# mt7621_integrated_router_v2_6_2025-04-17.net
KiCad netlist of a schematic drawn in EasyEDA Pro
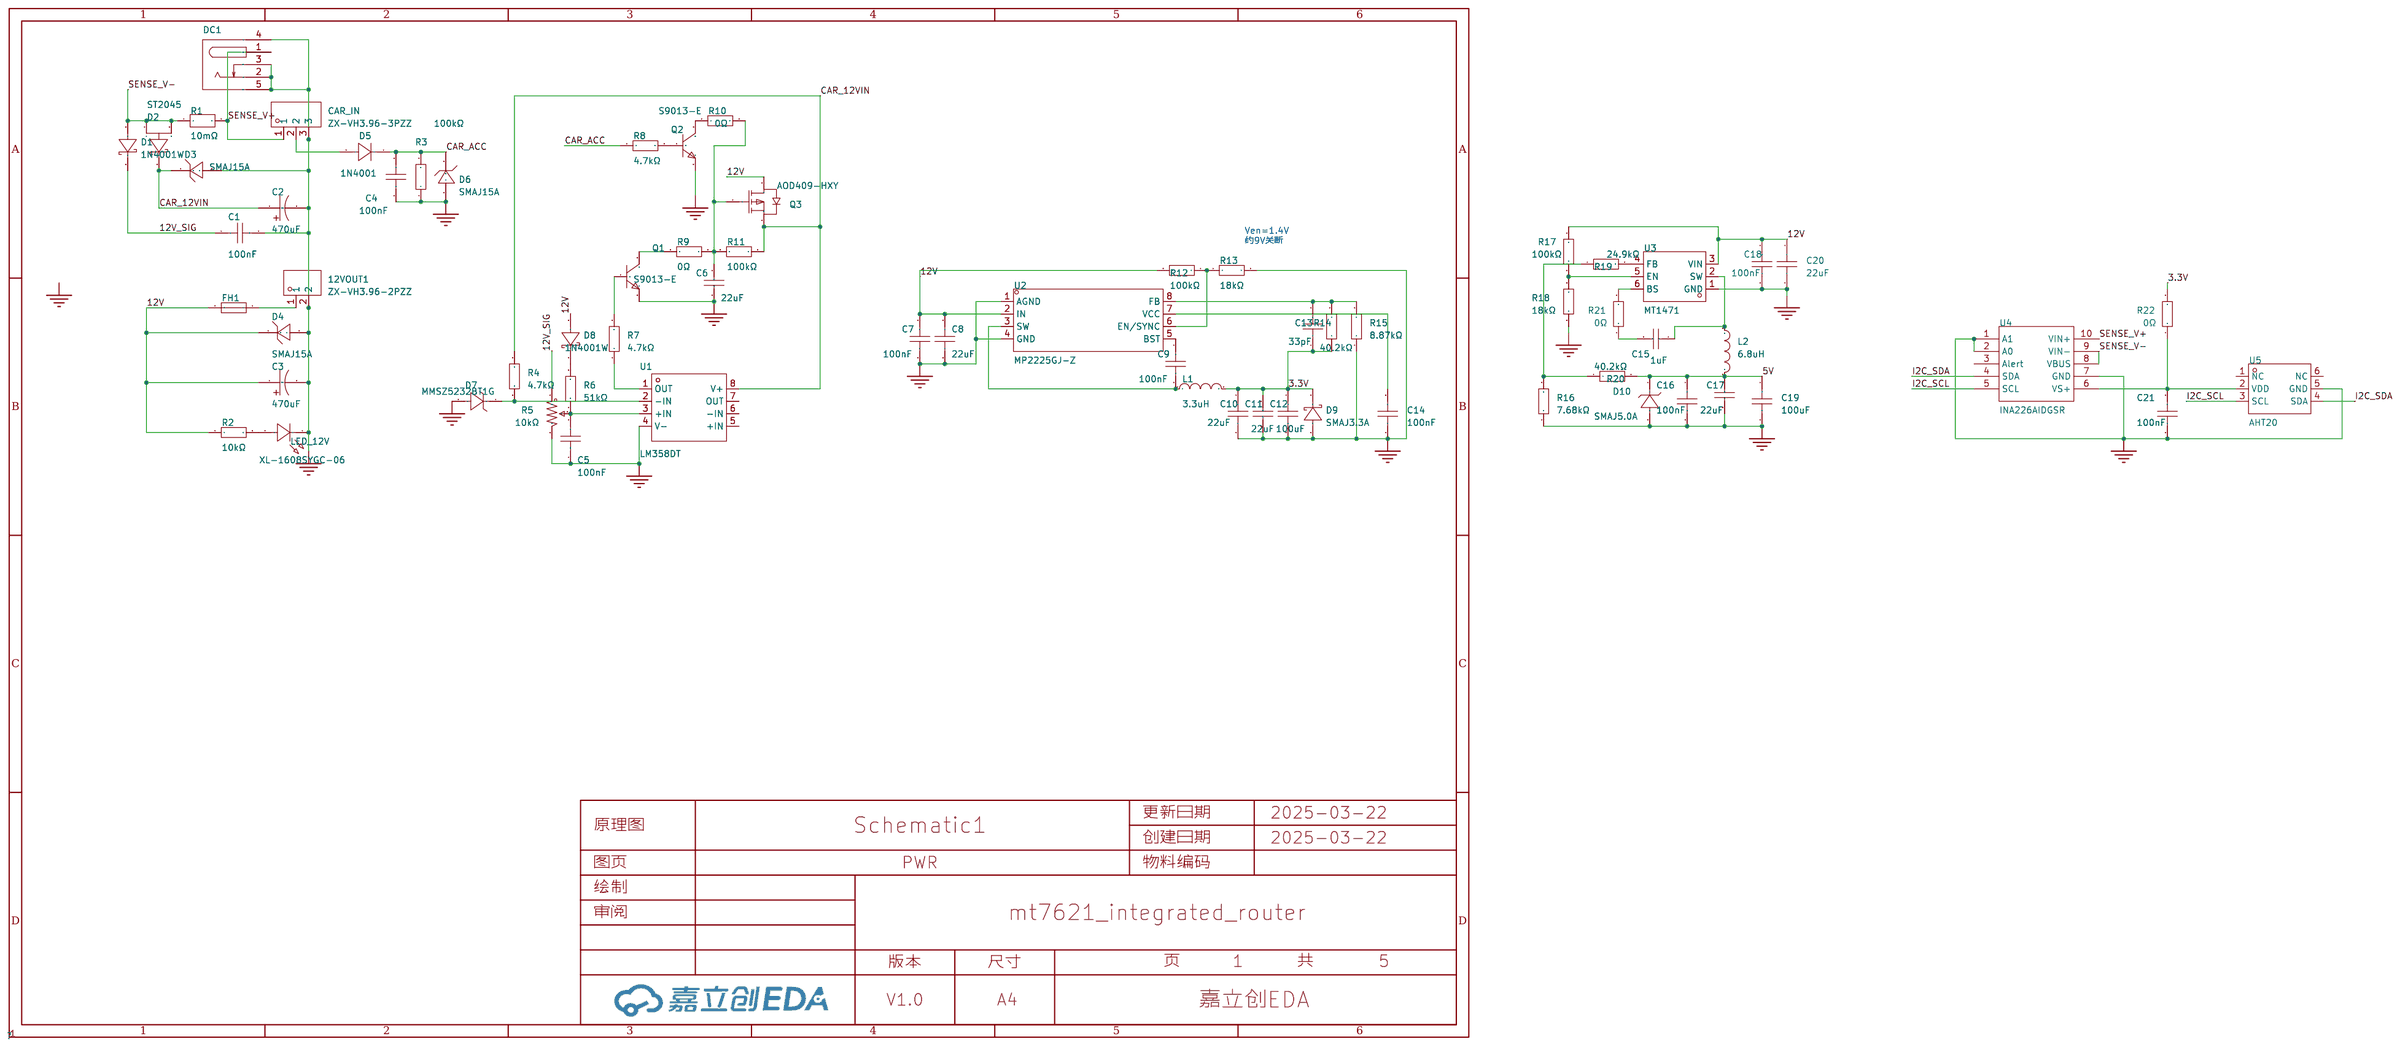
[diagram p0: PWR]
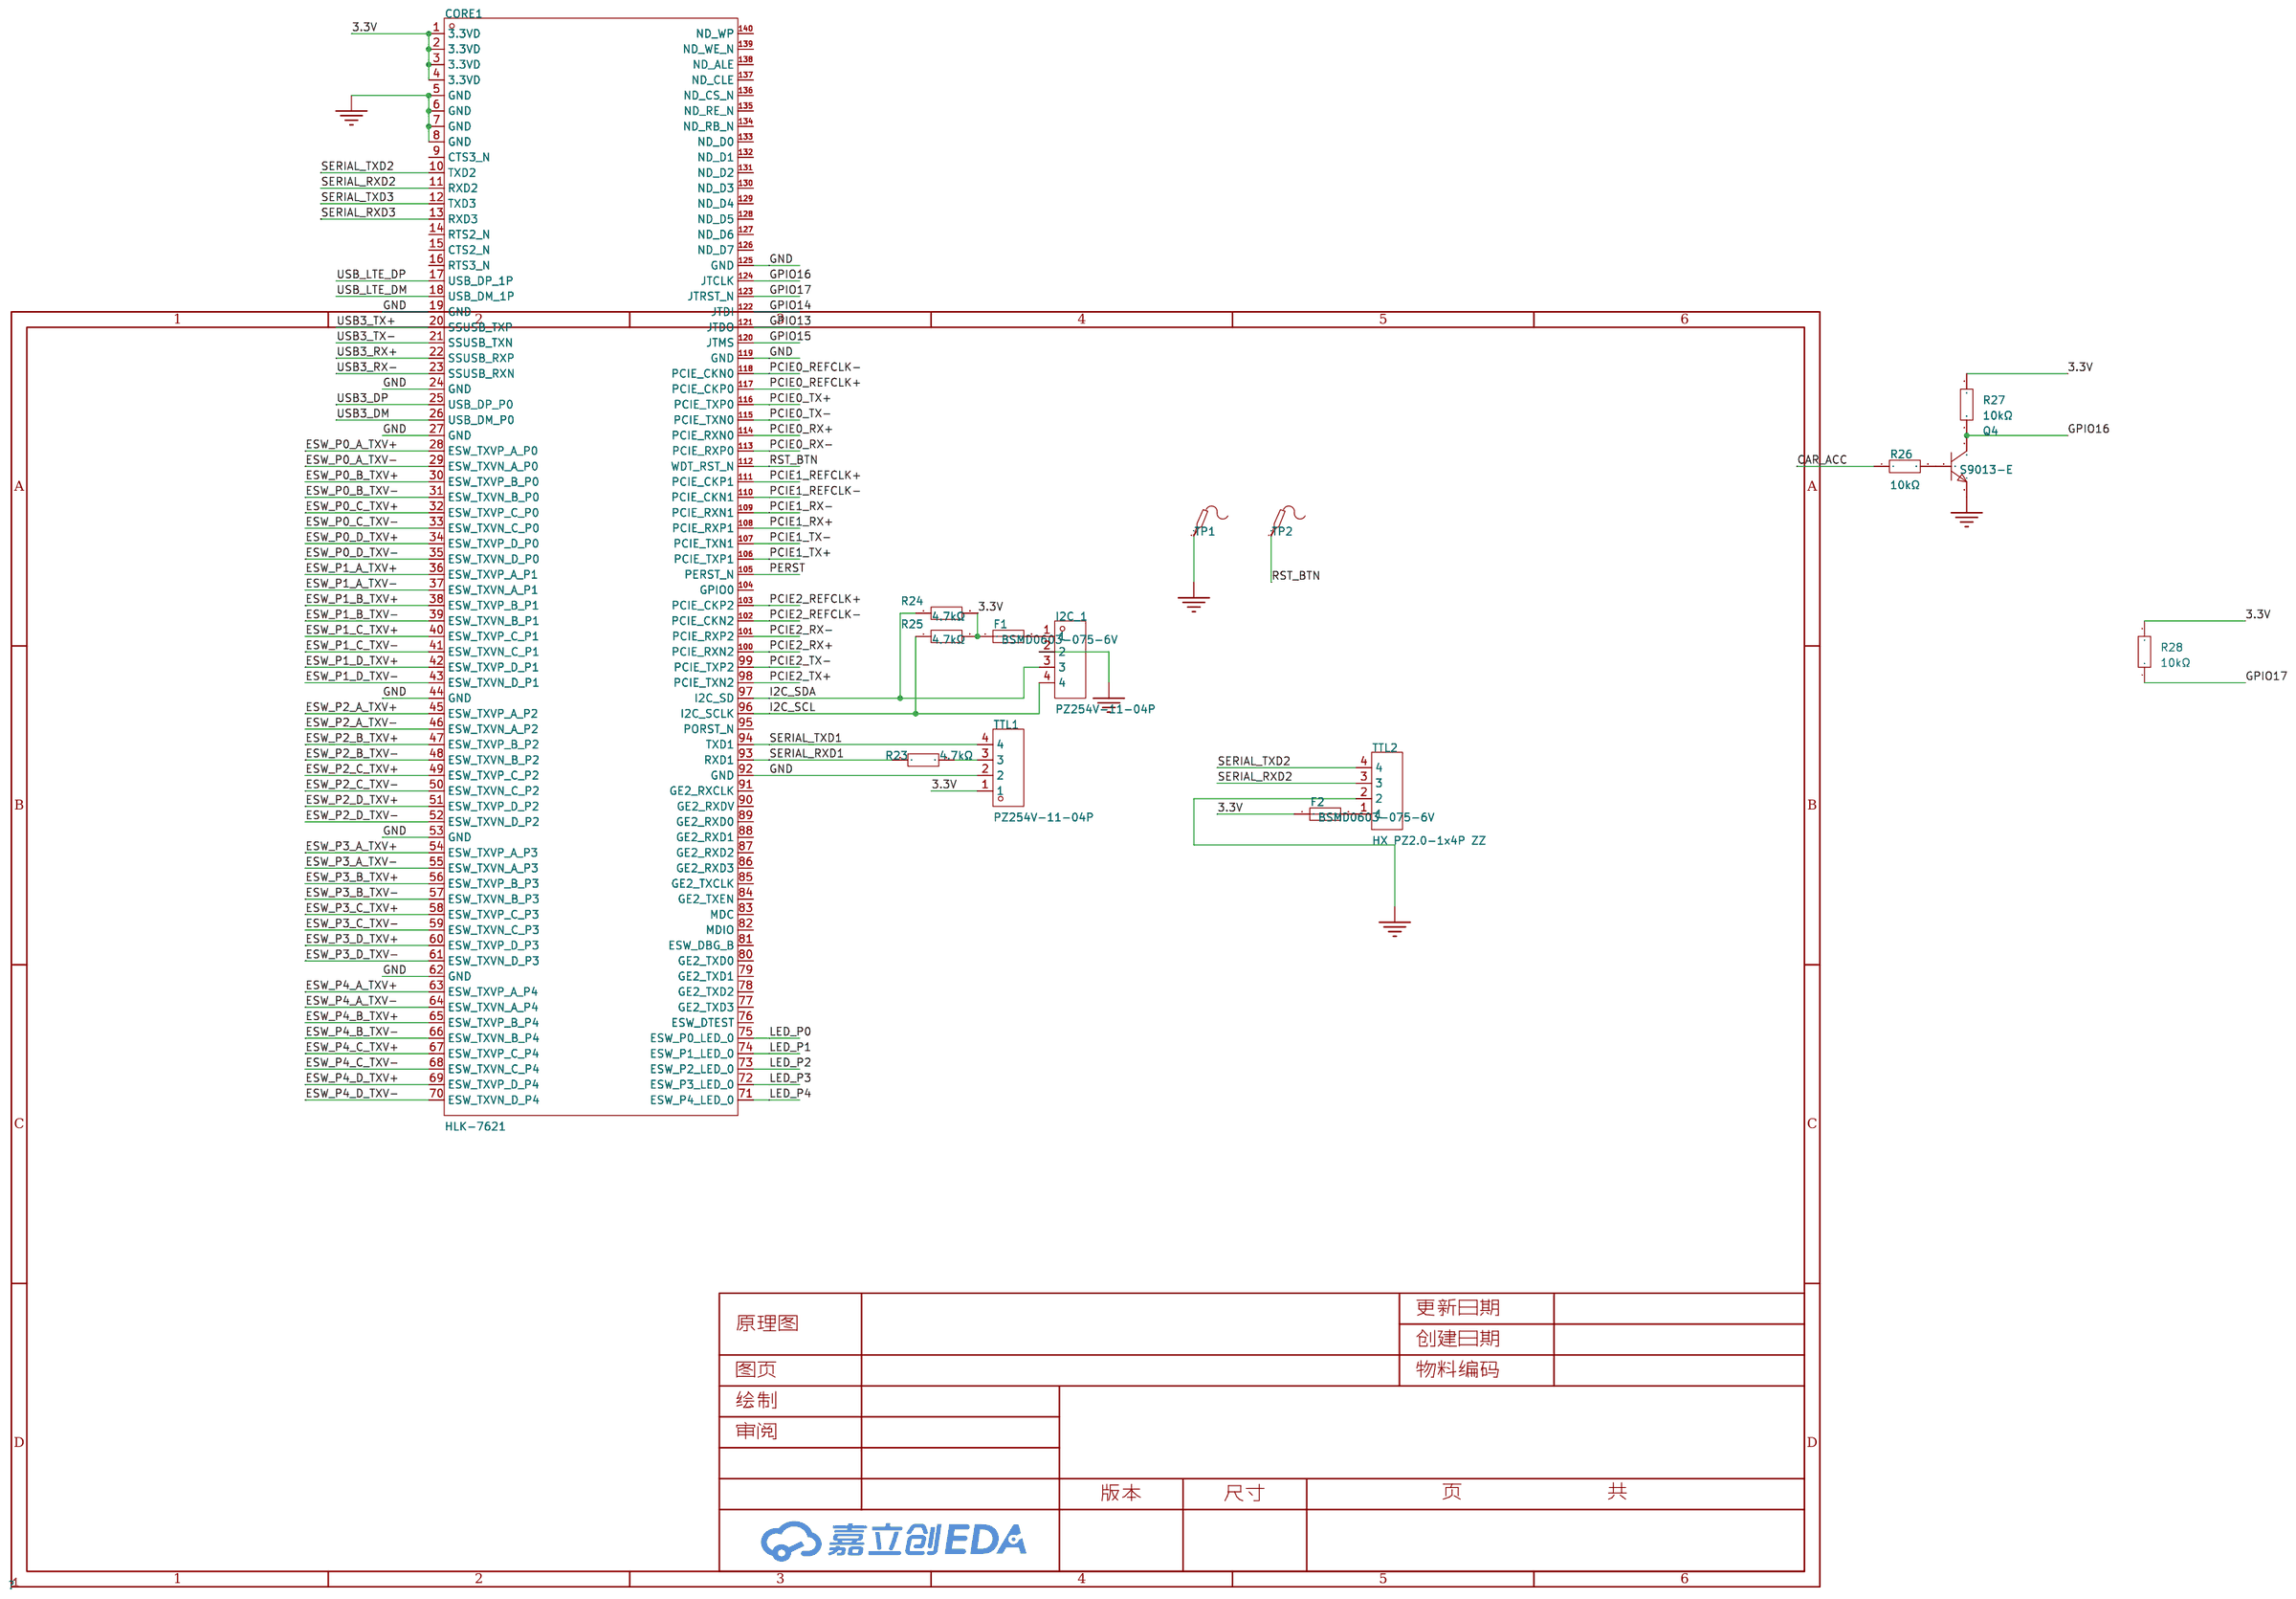
[diagram p1: Router]
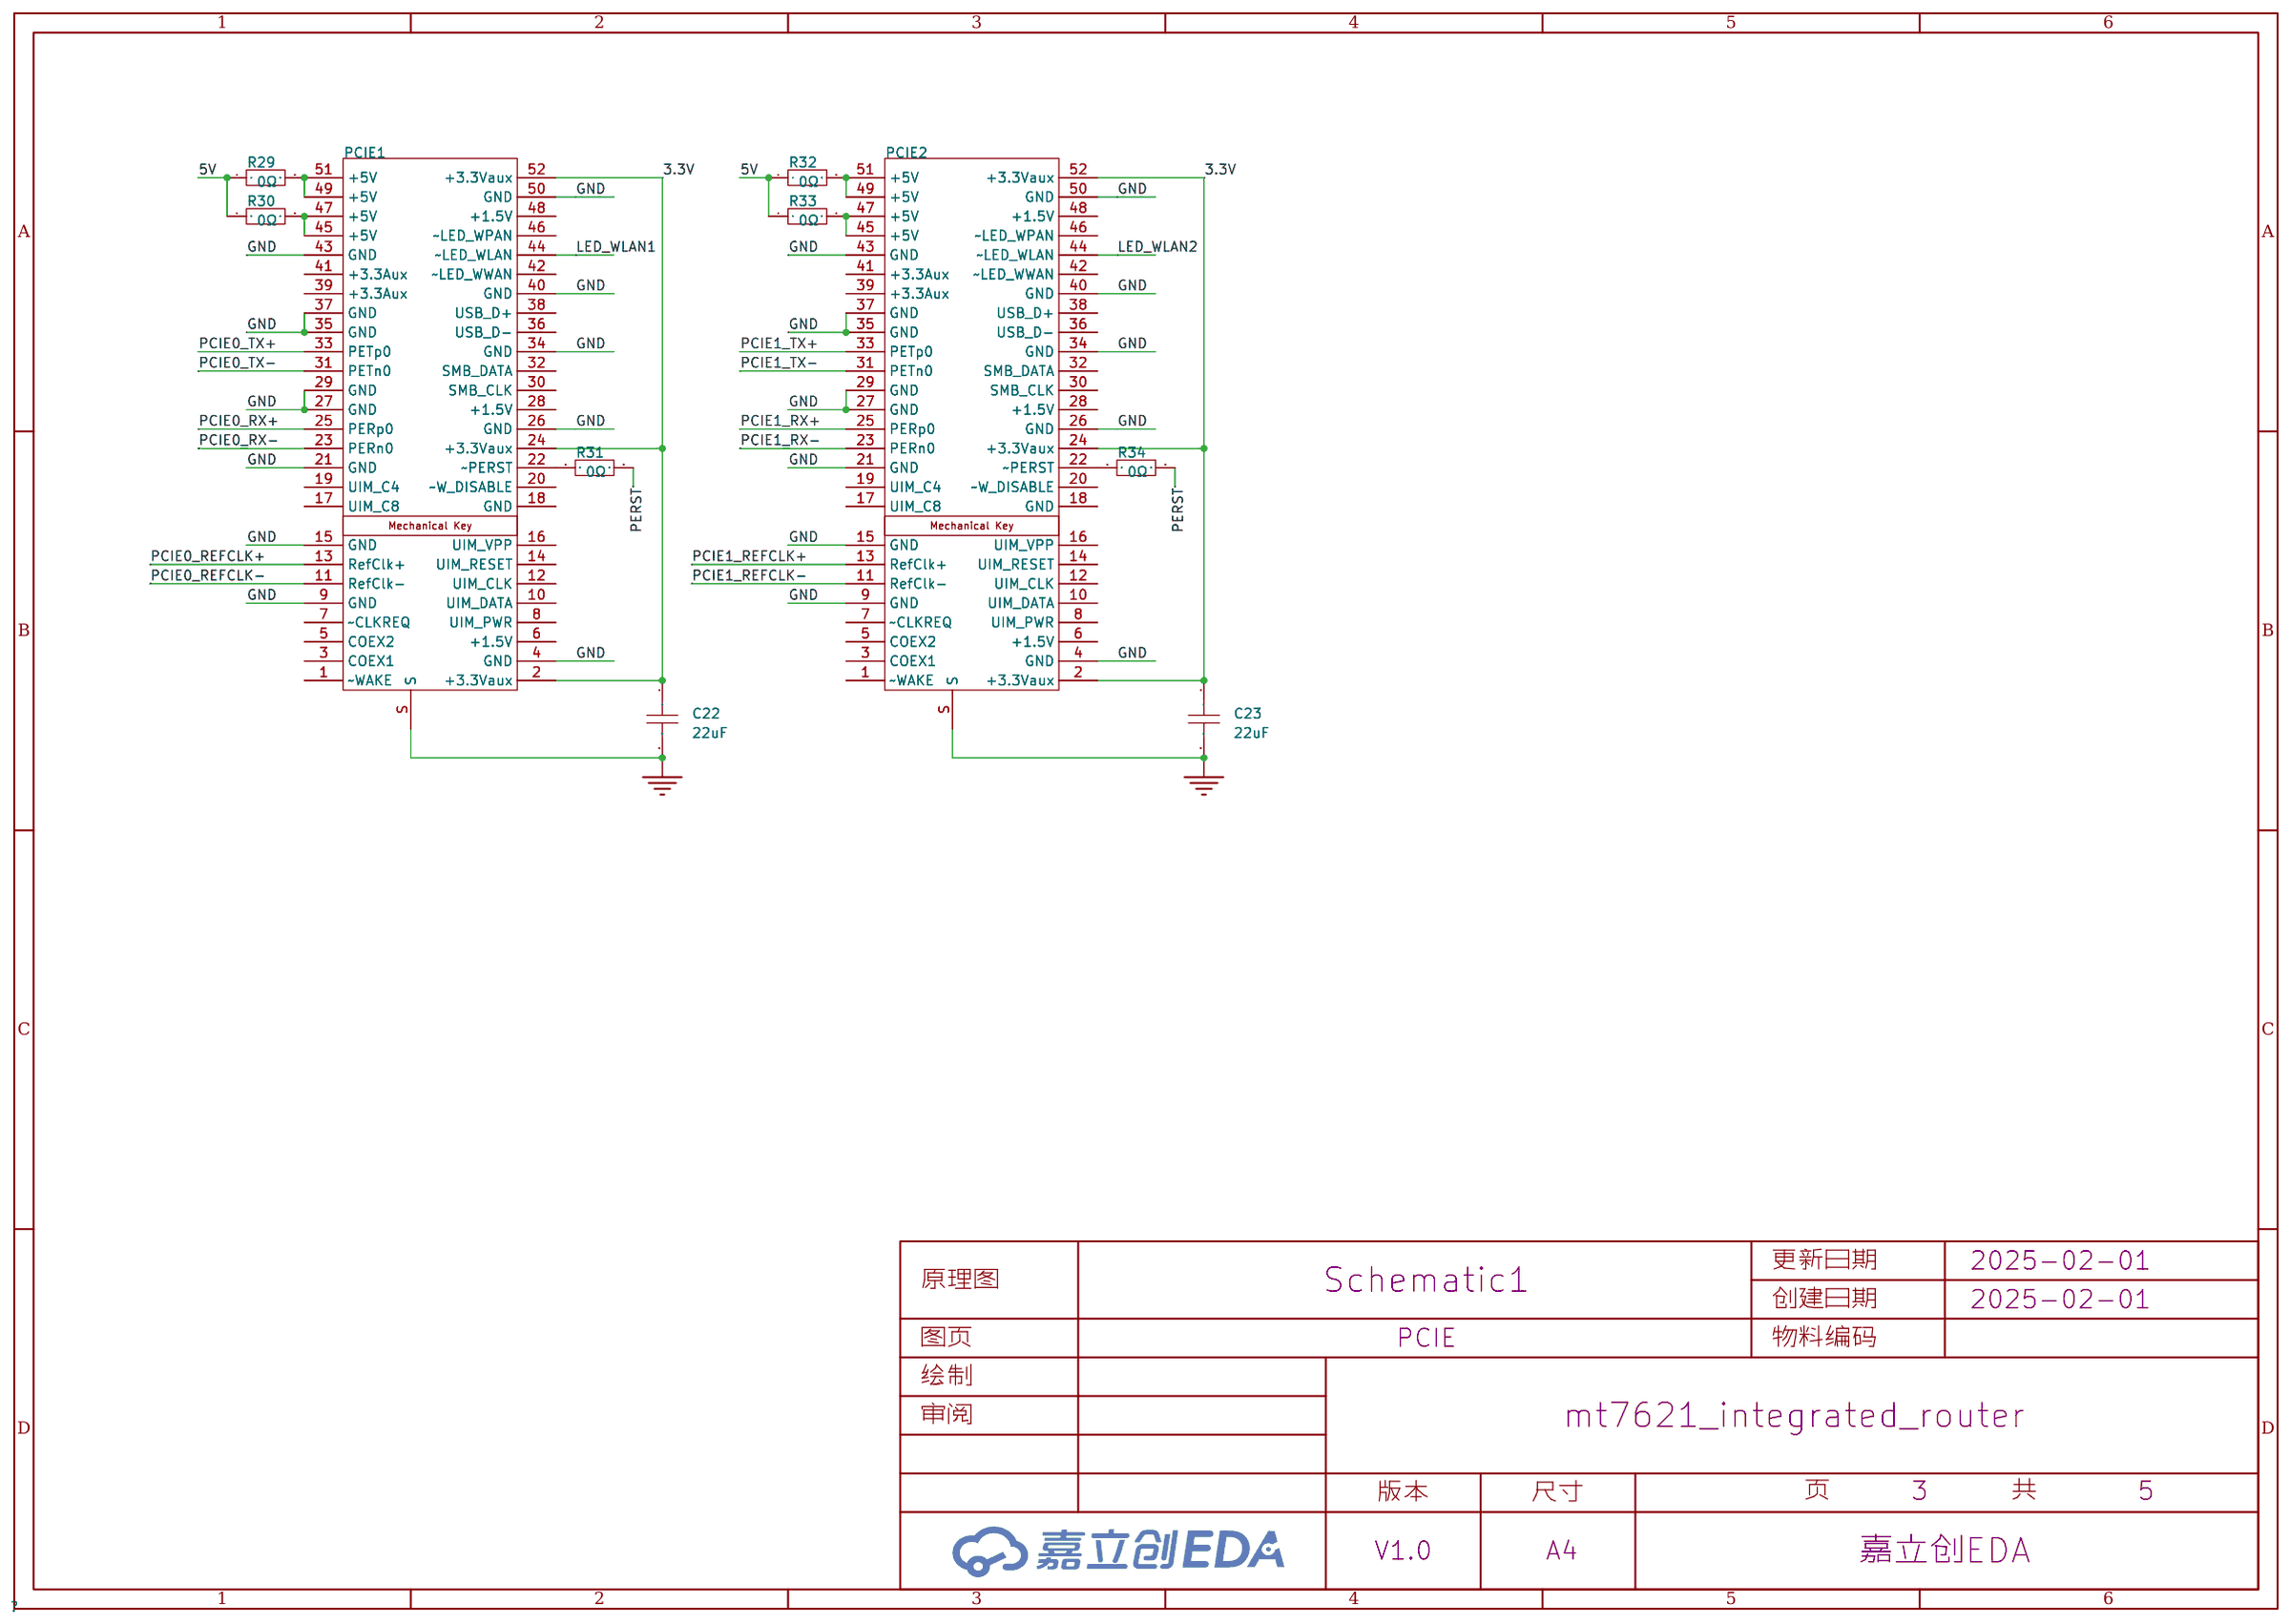
[diagram p2: PCIE]
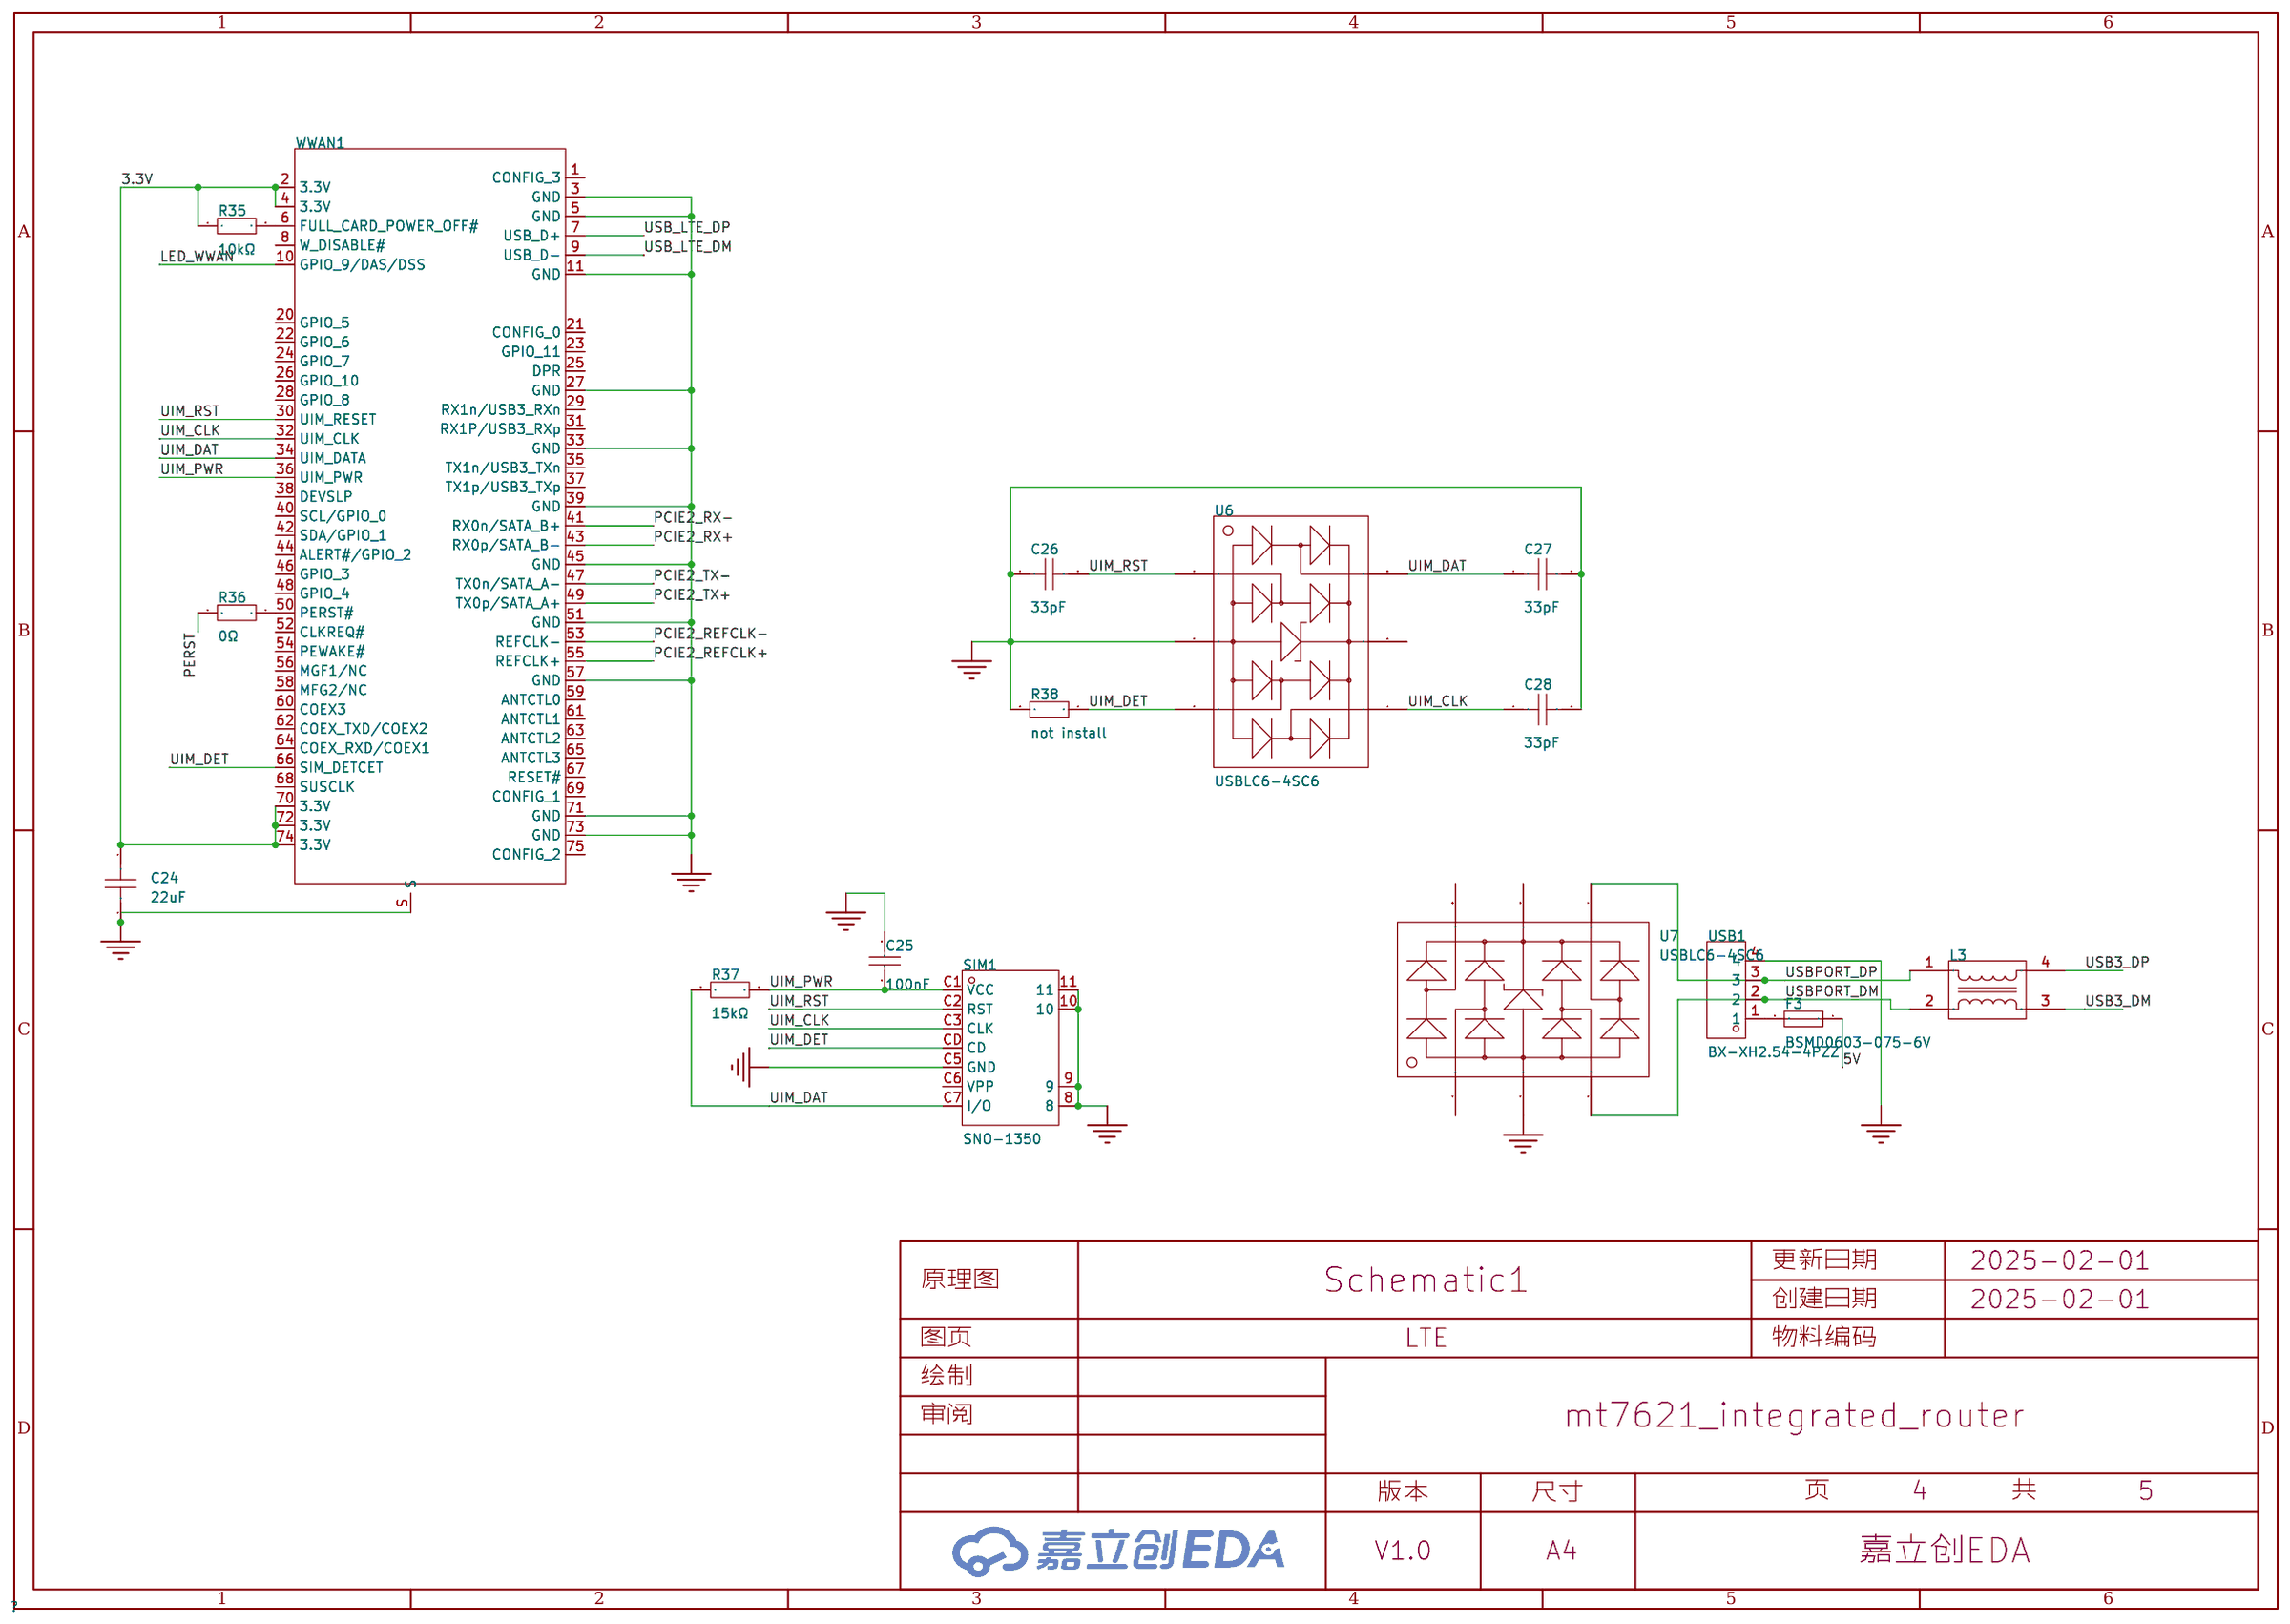
[diagram p3: LTE]
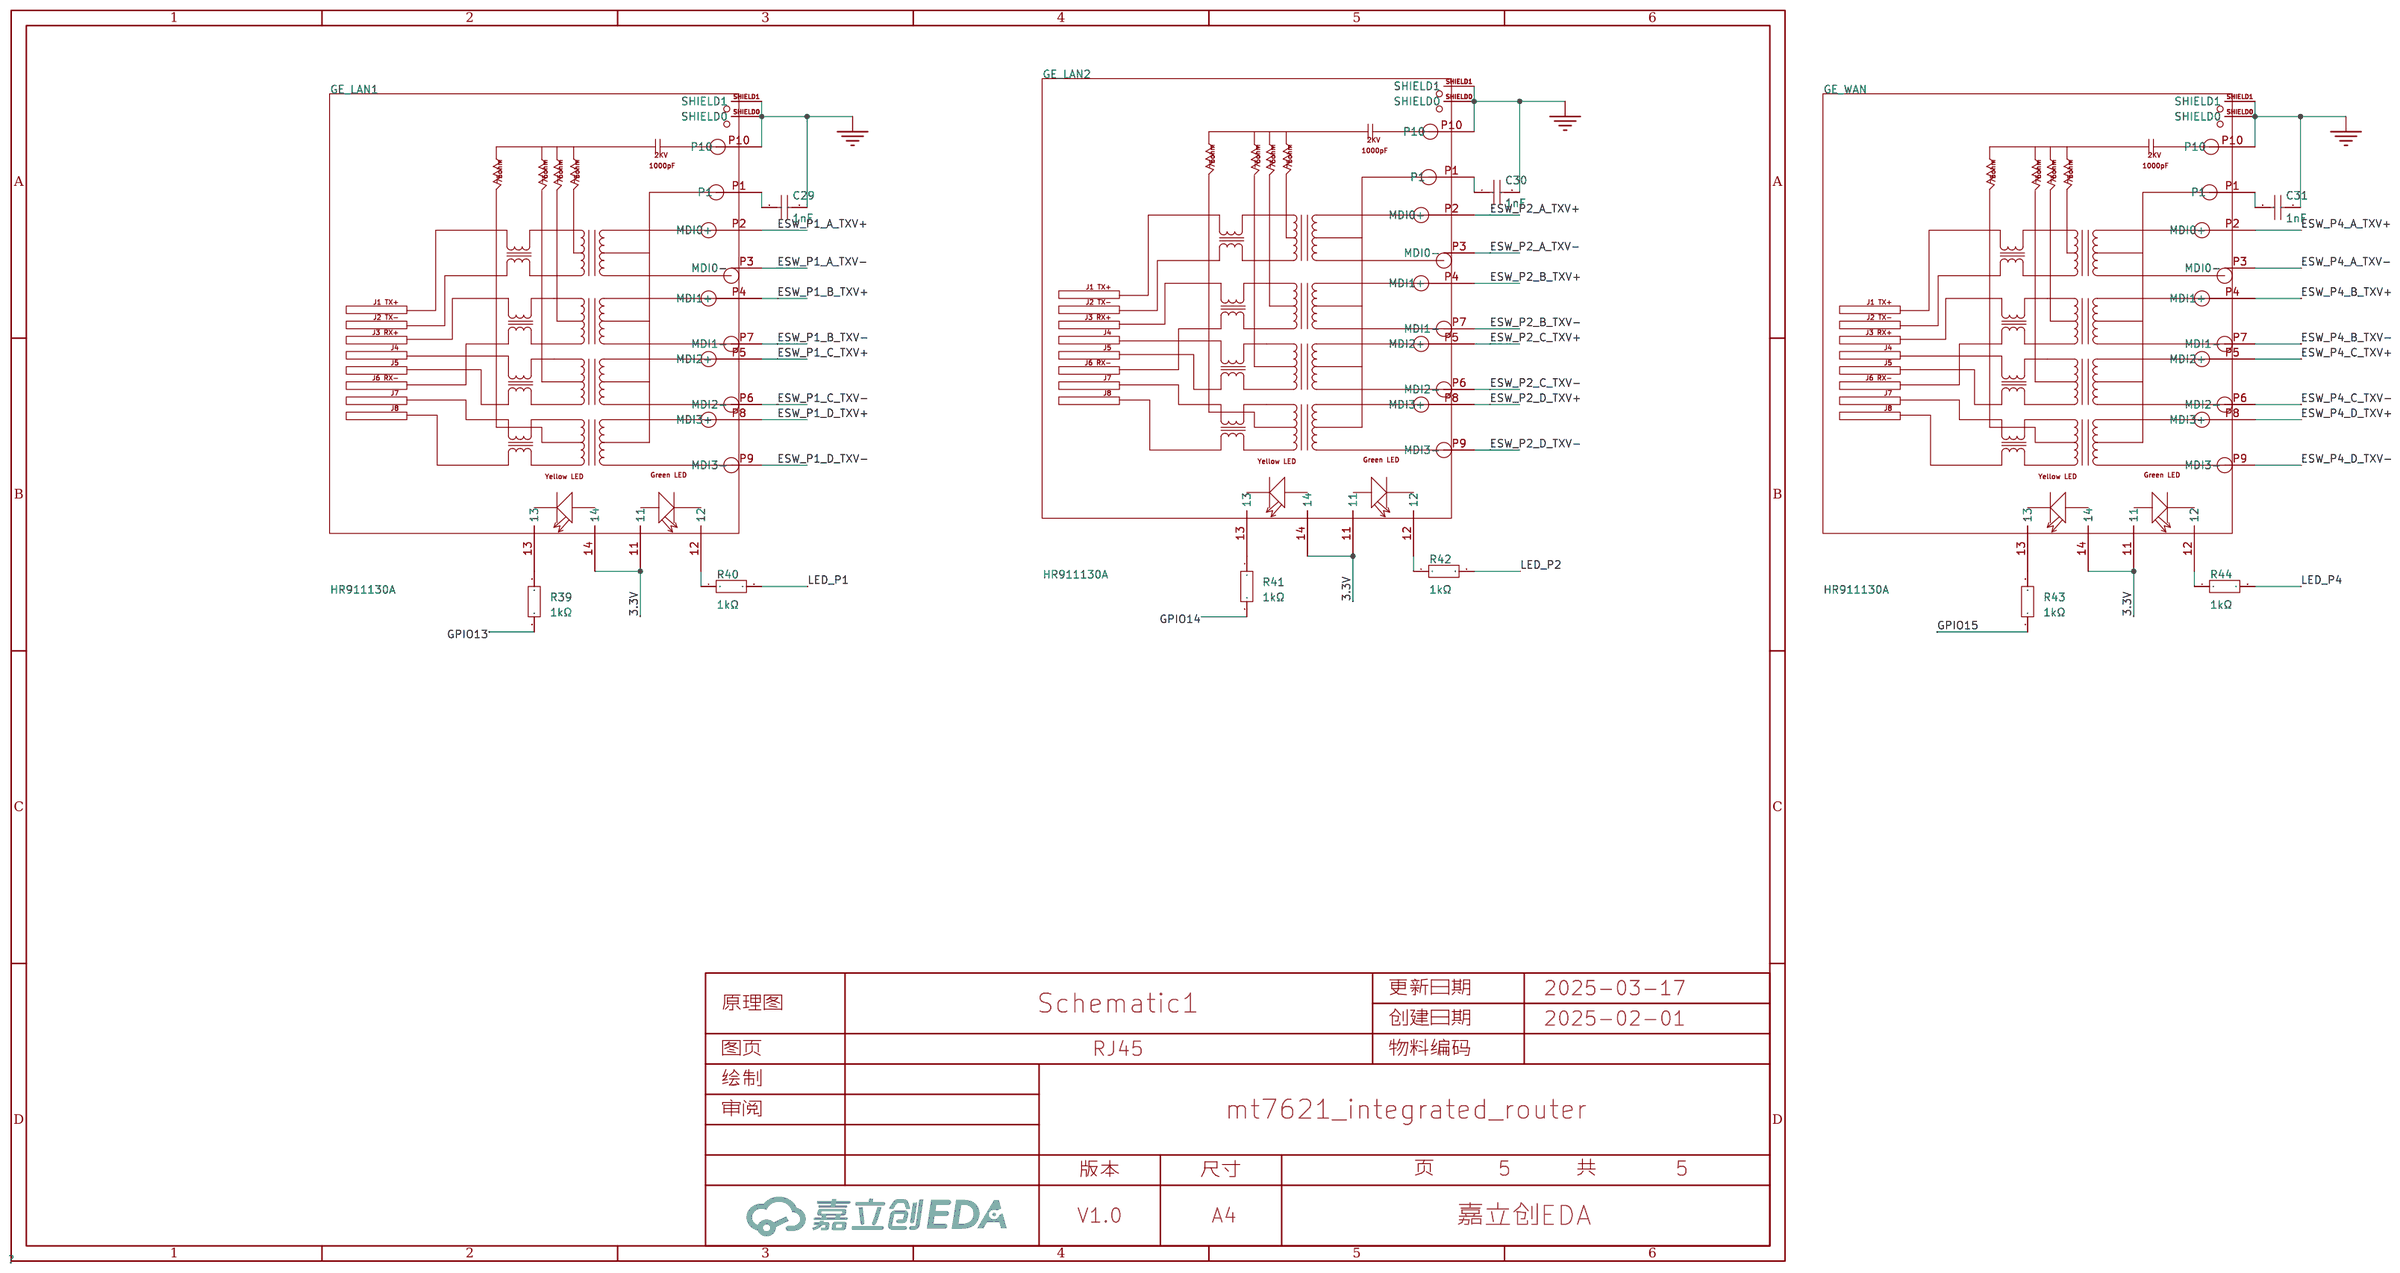
[diagram p4: RJ45]

(export (version "E")
  (design (tool "Eeschema 10.0.6"))
  (components
    (comp (ref "12VOUT1")
      (value "ZX-VH3.96-2PZZ")
      (footprint "easyedapro:CONN-TH_2P-P3.96_MEGASTAR_ZX-VH3.96-2PZZ")
      (description "插针结构:1x2P;间距:3.96mm;安装方式:直插;参考系列:VH;总PIN数:2P;排数:1;每排PIN数:2;行距:-;额定电流:3A;触头材质:黄铜;触头镀层:锡;工作温度范围:-;")
      (fields (field (name "Manufacturer") "Megastar(兆星)"))
      (libsource (lib "easyedapro") (part "ZX-VH3.96-2PZZ"))
    )
    (comp (ref "C1")
      (value "100nF")
      (footprint "easyedapro:C0603")
      (description "容值:100nF;精度:±10%;额定电压:25V;材质(温度系数):X7R;")
      (fields
        (field (name "Manufacturer Part") "CL10B104KA8NNNC")
        (field (name "Manufacturer") "SAMSUNG(三星)")
      )
      (libsource (lib "easyedapro") (part "CL10B104KA8NNNC"))
    )
    (comp (ref "C2")
      (value "470uF")
      (footprint "easyedapro:CAP-TH_BD8.0-P3.50-D0.6-FD")
      (description "类型:聚合物;容值:470uF;精度:±20%;额定电压:16V;纹波电流:5.4A@100kHz;等效串联电阻:8mΩ@100kHz;")
      (fields (field (name "Manufacturer Part") "16SEPG470M") (field (name "Manufacturer") "PANASONIC(松下)"))
      (libsource (lib "easyedapro") (part "16SEPG470M"))
    )
    (comp (ref "C3")
      (value "470uF")
      (footprint "easyedapro:CAP-TH_BD8.0-P3.50-D0.6-FD")
      (description "类型:聚合物;容值:470uF;精度:±20%;额定电压:16V;纹波电流:5.4A@100kHz;等效串联电阻:8mΩ@100kHz;")
      (fields (field (name "Manufacturer Part") "16SEPG470M") (field (name "Manufacturer") "PANASONIC(松下)"))
      (libsource (lib "easyedapro") (part "16SEPG470M"))
    )
    (comp (ref "C4")
      (value "100nF")
      (footprint "easyedapro:C0603")
      (description "容值:100nF;精度:±10%;额定电压:25V;材质(温度系数):X7R;")
      (fields
        (field (name "Manufacturer Part") "CL10B104KA8NNNC")
        (field (name "Manufacturer") "SAMSUNG(三星)")
      )
      (libsource (lib "easyedapro") (part "CL10B104KA8NNNC"))
    )
    (comp (ref "C5")
      (value "100nF")
      (footprint "easyedapro:C0603")
      (description "容值:100nF;精度:±10%;额定电压:25V;材质(温度系数):X7R;")
      (fields
        (field (name "Manufacturer Part") "CL10B104KA8NNNC")
        (field (name "Manufacturer") "SAMSUNG(三星)")
      )
      (libsource (lib "easyedapro") (part "CL10B104KA8NNNC"))
    )
    (comp (ref "C6")
      (value "22uF")
      (fields
        (field (name "Manufacturer Part") "CC0805MKX5R7BB226")
        (field (name "Manufacturer") "YAGEO(国巨)")
      )
      (libsource (lib "easyedapro") (part "cc0603mrx5r5bb226"))
    )
    (comp (ref "C7")
      (value "100nF")
      (footprint "easyedapro:C0603")
      (description "容值:100nF;精度:±10%;额定电压:25V;材质(温度系数):X7R;")
      (fields
        (field (name "Manufacturer Part") "CL10B104KA8NNNC")
        (field (name "Manufacturer") "SAMSUNG(三星)")
      )
      (libsource (lib "easyedapro") (part "CL10B104KA8NNNC"))
    )
    (comp (ref "C8")
      (value "22uF")
      (fields
        (field (name "Manufacturer Part") "CC0805MKX5R7BB226")
        (field (name "Manufacturer") "YAGEO(国巨)")
      )
      (libsource (lib "easyedapro") (part "cl21a226maqnnne"))
    )
    (comp (ref "C9")
      (value "100nF")
      (footprint "easyedapro:C0603")
      (description "容值:100nF;精度:±10%;额定电压:25V;材质(温度系数):X7R;")
      (fields
        (field (name "Manufacturer Part") "CL10B104KA8NNNC")
        (field (name "Manufacturer") "SAMSUNG(三星)")
      )
      (libsource (lib "easyedapro") (part "CL10B104KA8NNNC"))
    )
    (comp (ref "C10")
      (value "22uF")
      (footprint "easyedapro:C0805")
      (description "容值:22uF;精度:±20%;额定电压:16V;材质(温度系数):X5R;")
      (fields
        (field (name "Manufacturer Part") "CC0805MKX5R7BB226")
        (field (name "Manufacturer") "YAGEO(国巨)")
      )
      (libsource (lib "easyedapro") (part "CC0805MKX5R7BB226"))
    )
    (comp (ref "C11")
      (value "22uF")
      (fields
        (field (name "Manufacturer Part") "CC0805MKX5R7BB226")
        (field (name "Manufacturer") "YAGEO(国巨)")
      )
      (libsource (lib "easyedapro") (part "cc0603mrx5r5bb226"))
    )
    (comp (ref "C12")
      (value "100uF")
      (footprint "easyedapro:C1206")
      (description "容值:100uF;精度:±20%;额定电压:10V;材质(温度系数):X5R;")
      (fields
        (field (name "Manufacturer Part") "GRM31CR61A107ME05L")
        (field (name "Manufacturer") "muRata(村田)")
      )
      (libsource (lib "easyedapro") (part "GRM31CR61A107ME05L"))
    )
    (comp (ref "C13")
      (value "33pF")
      (footprint "easyedapro:C0603")
      (description "容值:33pF;精度:±5%;额定电压:50V;材质(温度系数):C0G;")
      (fields (field (name "Manufacturer Part") "0603CG330J500NT") (field (name "Manufacturer") "FH(风华)"))
      (libsource (lib "easyedapro") (part "0603CG330J500NT"))
    )
    (comp (ref "C14")
      (value "100nF")
      (footprint "easyedapro:C0603")
      (description "容值:100nF;精度:±10%;额定电压:50V;材质(温度系数):X7R;")
      (fields
        (field (name "Manufacturer Part") "CL10B104KB8NNNC")
        (field (name "Manufacturer") "SAMSUNG(三星)")
      )
      (libsource (lib "easyedapro") (part "CL10B104KB8NNNC"))
    )
    (comp (ref "C15")
      (value "1uF")
      (footprint "easyedapro:C0603")
      (description "容值:1uF;精度:±10%;额定电压:50V;材质(温度系数):X5R;")
      (fields
        (field (name "Manufacturer Part") "CL10A105KB8NNNC")
        (field (name "Manufacturer") "SAMSUNG(三星)")
      )
      (libsource (lib "easyedapro") (part "CL10A105KB8NNNC"))
    )
    (comp (ref "C16")
      (value "100nF")
      (footprint "easyedapro:C0603")
      (description "容值:100nF;精度:±10%;额定电压:25V;材质(温度系数):X7R;")
      (fields
        (field (name "Manufacturer Part") "CL10B104KA8NNNC")
        (field (name "Manufacturer") "SAMSUNG(三星)")
      )
      (libsource (lib "easyedapro") (part "CL10B104KA8NNNC"))
    )
    (comp (ref "C17")
      (value "22uF")
      (fields
        (field (name "Manufacturer Part") "CC0805MKX5R7BB226")
        (field (name "Manufacturer") "YAGEO(国巨)")
      )
      (libsource (lib "easyedapro") (part "cc0603mrx5r5bb226"))
    )
    (comp (ref "C18")
      (value "100nF")
      (footprint "easyedapro:C0603")
      (description "容值:100nF;精度:±10%;额定电压:25V;材质(温度系数):X7R;")
      (fields
        (field (name "Manufacturer Part") "CL10B104KA8NNNC")
        (field (name "Manufacturer") "SAMSUNG(三星)")
      )
      (libsource (lib "easyedapro") (part "CL10B104KA8NNNC"))
    )
    (comp (ref "C19")
      (value "100uF")
      (footprint "easyedapro:C1206")
      (description "容值:100uF;精度:±20%;额定电压:10V;材质(温度系数):X5R;")
      (fields
        (field (name "Manufacturer Part") "GRM31CR61A107ME05L")
        (field (name "Manufacturer") "muRata(村田)")
      )
      (libsource (lib "easyedapro") (part "GRM31CR61A107ME05L"))
    )
    (comp (ref "C20")
      (value "22uF")
      (fields
        (field (name "Manufacturer Part") "CC0805MKX5R7BB226")
        (field (name "Manufacturer") "YAGEO(国巨)")
      )
      (libsource (lib "easyedapro") (part "cl21a226maqnnne"))
    )
    (comp (ref "C21")
      (value "100nF")
      (footprint "easyedapro:C0603")
      (description "容值:100nF;精度:±10%;额定电压:25V;材质(温度系数):X7R;")
      (fields
        (field (name "Manufacturer Part") "CL10B104KA8NNNC")
        (field (name "Manufacturer") "SAMSUNG(三星)")
      )
      (libsource (lib "easyedapro") (part "CL10B104KA8NNNC"))
    )
    (comp (ref "CAR_IN")
      (value "ZX-VH3.96-3PZZ")
      (footprint "easyedapro:CONN-TH_3P-P3.96_MEGASTAR_ZX-VH3.96-3PZZ")
      (description "插针结构:1x3P;间距:3.96mm;安装方式:直插;参考系列:VH;总PIN数:3P;排数:1;每排PIN数:3;行距:-;额定电流:3A;触头材质:黄铜;触头镀层:锡;工作温度范围:-;")
      (fields (field (name "Manufacturer") "Megastar(兆星)"))
      (libsource (lib "easyedapro") (part "ZX-VH3.96-3PZZ"))
    )
    (comp (ref "D1")
      (value "1N4001W")
      (footprint "easyedapro:SOD-123FL_L2.7-W1.8-LS3.8-RD")
      (description "二极管配置:独立式;正向压降(Vf):1V@1.0A;直流反向耐压(Vr):50V;整流电流:1A;")
      (fields (field (name "Manufacturer") "宏迦橙"))
      (libsource (lib "easyedapro") (part "1N4001W_C18199085"))
    )
    (comp (ref "D2")
      (value "ST2045")
      (footprint "easyedapro:TO-277_3P-L5.4-W4.0-LS6.5-BR")
      (description "二极管配置:独立式;正向压降(Vf):470mV@20A;直流反向耐压(Vr):45V;整流电流:20A;")
      (fields (field (name "Manufacturer") "MDD(辰达半导体)"))
      (libsource (lib "easyedapro") (part "ST2045"))
    )
    (comp (ref "D3")
      (value "SMAJ15A")
      (footprint "easyedapro:SMA_L4.3-W2.6-LS5.2-RD")
      (description "反向截止电压(Vrwm):15V;最大钳位电压:24.4V;峰值脉冲电流(Ipp):16.4A;峰值脉冲功率(Ppp):400W;击穿电压:16.7V;")
      (fields (field (name "Manufacturer") "Littelfuse(美国力特)"))
      (libsource (lib "easyedapro") (part "SMAJ15A-C148216"))
    )
    (comp (ref "D4")
      (value "SMAJ15A")
      (footprint "easyedapro:SMA_L4.3-W2.6-LS5.2-RD")
      (description "反向截止电压(Vrwm):15V;最大钳位电压:24.4V;峰值脉冲电流(Ipp):16.4A;峰值脉冲功率(Ppp):400W;击穿电压:16.7V;")
      (fields (field (name "Manufacturer") "Littelfuse(美国力特)"))
      (libsource (lib "easyedapro") (part "SMAJ15A-C148216"))
    )
    (comp (ref "D5")
      (value "1N4001")
      (footprint "easyedapro:SMA_L4.3-W2.5-LS5.0-RD")
      (description "二极管配置:独立式;正向压降(Vf):1.1V@1A;直流反向耐压(Vr):50V;整流电流:1A;")
      (fields (field (name "Manufacturer") "TWGMC(台湾迪嘉)"))
      (libsource (lib "easyedapro") (part "1N4001_C727079"))
    )
    (comp (ref "D6")
      (value "SMAJ15A")
      (footprint "easyedapro:SMA_L4.3-W2.6-LS5.2-RD")
      (description "反向截止电压(Vrwm):15V;最大钳位电压:24.4V;峰值脉冲电流(Ipp):16.4A;峰值脉冲功率(Ppp):400W;击穿电压:16.7V;")
      (fields (field (name "Manufacturer") "Littelfuse(美国力特)"))
      (libsource (lib "easyedapro") (part "SMAJ15A-C148216"))
    )
    (comp (ref "D7")
      (value "MMSZ5232BT1G")
      (footprint "easyedapro:SOD-123_L2.7-W1.6-LS3.7-RD")
      (description "二极管配置:独立式;稳压值(标称值):5.6V;稳压值(范围):5.32V~5.88V;功率(Pd):500mW;")
      (fields (field (name "Manufacturer") "onsemi(安森美)"))
      (libsource (lib "easyedapro") (part "MMSZ5232BT1G"))
    )
    (comp (ref "D8")
      (value "1N4001W")
      (footprint "easyedapro:SOD-123FL_L2.7-W1.8-LS3.8-RD")
      (description "二极管配置:独立式;正向压降(Vf):1V@1.0A;直流反向耐压(Vr):50V;整流电流:1A;")
      (fields (field (name "Manufacturer") "宏迦橙"))
      (libsource (lib "easyedapro") (part "1N4001W_C18199085"))
    )
    (comp (ref "D9")
      (value "SMAJ3.3A")
      (footprint "easyedapro:SMA-SMD_L4.4-W2.7-LS5.4-RD")
      (description "极性:单向;反向截止电压(Vrwm):3.3V;钳位电压:8.7V@47.6A;峰值脉冲电流(Ipp):47.6A;峰值脉冲功率(Ppp):400W;击穿电压:4.2V;")
      (fields (field (name "Manufacturer") "BORN(伯恩半导体)"))
      (libsource (lib "easyedapro") (part "SMAJ3.3A_C18199544"))
    )
    (comp (ref "D10")
      (value "SMAJ5.0A")
      (footprint "easyedapro:SMA_L4.3-W2.6-LS5.0-RD")
      (description "极性:单向;反向截止电压(Vrwm):5V;钳位电压:9.2V;峰值脉冲电流(Ipp):43.5A;峰值脉冲功率(Ppp):400W;击穿电压:6.4V;")
      (fields (field (name "Manufacturer") "宏嘉诚"))
      (libsource (lib "easyedapro") (part "SMAJ5.0A_C19077523"))
    )
    (comp (ref "DC1")
      (value "{ManufacturerPart!}")
      (footprint "easyedapro:DC-IN-TH_DC-044A-20A")
      (description "触点内径:2mm;触点外径:0.9mm;")
      (fields (field (name "Manufacturer Part") "DC-044A-20A") (field (name "Manufacturer") "韩国韩荣"))
      (libsource (lib "easyedapro") (part "DC-044A-20A"))
    )
    (comp (ref "FH1")
      (value "01550900M")
      (footprint "easyedapro:FUSE-SMD_L9.8-W5.0")
      (description "保险丝座类型:-;保险丝类型:-;保险丝尺寸:-;")
      (fields (field (name "Manufacturer") "Littelfuse(美国力特)"))
      (libsource (lib "easyedapro") (part "01550900M"))
    )
    (comp (ref "L1")
      (value "3.3uH")
      (footprint "easyedapro:IND-SMD_L7.0-W6.6")
      (description "电感值:3.3uH;精度:±20%;额定电流:8.5A;饱和电流(Isat):9.5A;类型:一体成型电感;")
      (fields (field (name "Manufacturer Part") "FXL0630-3R3-M") (field (name "Manufacturer") "cjiang(长江微电)"))
      (libsource (lib "easyedapro") (part "FXL0630-3R3-M"))
    )
    (comp (ref "L2")
      (value "6.8uH")
      (footprint "easyedapro:IND-SMD_L7.0-W6.6")
      (description "电感值:6.8uH;精度:±20%;额定电流:5A;饱和电流(Isat):6A;类型:一体成型电感;")
      (fields (field (name "Manufacturer Part") "FXL0630-6R8-M") (field (name "Manufacturer") "cjiang(长江微电)"))
      (libsource (lib "easyedapro") (part "FXL0630-6R8-M"))
    )
    (comp (ref "LED_12V")
      (value "XL-1608SYGC-06")
      (footprint "easyedapro:LED0603-RD_GREEN")
      (description "发光颜色:普绿/黄绿;主波长:570nm~573nm;色温:2800K~3160K;功率:55mW;安装方式:正贴;")
      (fields (field (name "Manufacturer") "XINGLIGHT(成兴光)"))
      (libsource (lib "easyedapro") (part "XL-1608SYGC-06"))
    )
    (comp (ref "Q1")
      (value "S9013-E")
      (footprint "easyedapro:SOT-23-3_L2.9-W1.3-P1.90-LS2.4-BR")
      (description "晶体管类型:NPN;集电极电流(Ic):500mA;集射极击穿电压(Vceo):25V;功率(Pd):300mW;直流电流增益(hFE@Ic,Vce):120@50mA,1V;")
      (fields (field (name "Manufacturer") "MDD(辰达半导体)"))
      (libsource (lib "easyedapro") (part "S9013-E"))
    )
    (comp (ref "Q2")
      (value "S9013-E")
      (footprint "easyedapro:SOT-23-3_L2.9-W1.3-P1.90-LS2.4-BR")
      (description "晶体管类型:NPN;集电极电流(Ic):500mA;集射极击穿电压(Vceo):25V;功率(Pd):300mW;直流电流增益(hFE@Ic,Vce):120@50mA,1V;")
      (fields (field (name "Manufacturer") "MDD(辰达半导体)"))
      (libsource (lib "easyedapro") (part "S9013-E"))
    )
    (comp (ref "Q3")
      (value "AOD409-HXY")
      (footprint "easyedapro:TO-252-2_L6.6-W6.1-P4.57-LS9.9-TL-CW")
      (description "类型:1个P沟道;漏源电压(Vdss):60V;连续漏极电流(Id):50A;导通电阻(RDS(on)):24mΩ@10V,18A;耗散功率(Pd):52.1W;阈值电压(Vgs(th)):1V;")
      (fields (field (name "Manufacturer") "HXY MOSFET(华轩阳电子)"))
      (libsource (lib "easyedapro") (part "AOD409-HXY"))
    )
    (comp (ref "R1")
      (value "10mΩ")
      (footprint "easyedapro:R1206")
      (description "电阻类型:采样电阻;阻值:10mΩ;精度:±1%;额定压降:-;功率:1W;温度系数:±50ppm/°C;安装方式:-;")
      (fields (field (name "Manufacturer Part") "FRM121WFR010TM") (field (name "Manufacturer") "FOJAN(富捷)"))
      (libsource (lib "easyedapro") (part "FRM121WFR010TM"))
    )
    (comp (ref "R2")
      (value "10kΩ")
      (footprint "easyedapro:R0603")
      (description "电阻类型:厚膜电阻;阻值:10kΩ;精度:±1%;功率:100mW;")
      (fields
        (field (name "Manufacturer Part") "0603WAF1002T5E")
        (field (name "Manufacturer") "UNI-ROYAL(厚声)")
      )
      (libsource (lib "easyedapro") (part "0603WAF1002T5E"))
    )
    (comp (ref "R3")
      (value "100kΩ")
      (footprint "easyedapro:R0603")
      (description "电阻类型:厚膜电阻;阻值:100kΩ;精度:±1%;功率:100mW;最大工作电压:75V;温度系数:±100ppm/°C;")
      (fields
        (field (name "Manufacturer Part") "0603WAF1003T5E")
        (field (name "Manufacturer") "UNI-ROYAL(厚声)")
      )
      (libsource (lib "easyedapro") (part "0603WAF1003T5E"))
    )
    (comp (ref "R4")
      (value "4.7kΩ")
      (fields
        (field (name "Manufacturer Part") "0603WAF4701T5E")
        (field (name "Manufacturer") "UNI-ROYAL(厚声)")
      )
      (libsource (lib "easyedapro") (part "0603WAF4701T5E"))
    )
    (comp (ref "R5")
      (value "10kΩ")
      (footprint "easyedapro:RES-ADJ-TH_3P-L10.0-W10.0-P2.50-L")
      (description "阻值:10kΩ;精度:±10%;")
      (fields (field (name "Manufacturer Part") "3296W-1-103") (field (name "Manufacturer") "BOCHEN(博晨)"))
      (libsource (lib "easyedapro") (part "3296W-1-103"))
    )
    (comp (ref "R6")
      (value "51kΩ")
      (footprint "easyedapro:R0603")
      (description "电阻类型:厚膜电阻;阻值:51kΩ;精度:±1%;功率:100mW;最大工作电压:75V;温度系数:±100ppm/°C;")
      (fields
        (field (name "Manufacturer Part") "0603WAF5102T5E")
        (field (name "Manufacturer") "UNI-ROYAL(厚声)")
      )
      (libsource (lib "easyedapro") (part "0603WAF5102T5E"))
    )
    (comp (ref "R7")
      (value "4.7kΩ")
      (fields
        (field (name "Manufacturer Part") "0603WAF4701T5E")
        (field (name "Manufacturer") "UNI-ROYAL(厚声)")
      )
      (libsource (lib "easyedapro") (part "0603WAF4701T5E"))
    )
    (comp (ref "R8")
      (value "4.7kΩ")
      (fields
        (field (name "Manufacturer Part") "0603WAF4701T5E")
        (field (name "Manufacturer") "UNI-ROYAL(厚声)")
      )
      (libsource (lib "easyedapro") (part "0603WAF4701T5E"))
    )
    (comp (ref "R9")
      (value "0Ω")
      (footprint "easyedapro:R0603")
      (description "电阻类型:厚膜电阻;阻值:0Ω;精度:±1%;功率:100mW;")
      (fields
        (field (name "Manufacturer Part") "0603WAF0000T5E")
        (field (name "Manufacturer") "UNI-ROYAL(厚声)")
      )
      (libsource (lib "easyedapro") (part "0603WAF0000T5E"))
    )
    (comp (ref "R10")
      (value "0Ω")
      (footprint "easyedapro:R0603")
      (description "电阻类型:厚膜电阻;阻值:0Ω;精度:±1%;功率:100mW;")
      (fields
        (field (name "Manufacturer Part") "0603WAF0000T5E")
        (field (name "Manufacturer") "UNI-ROYAL(厚声)")
      )
      (libsource (lib "easyedapro") (part "0603WAF0000T5E"))
    )
    (comp (ref "R11")
      (value "100kΩ")
      (footprint "easyedapro:R0603")
      (description "电阻类型:厚膜电阻;阻值:100kΩ;精度:±1%;功率:100mW;最大工作电压:75V;温度系数:±100ppm/°C;")
      (fields
        (field (name "Manufacturer Part") "0603WAF1003T5E")
        (field (name "Manufacturer") "UNI-ROYAL(厚声)")
      )
      (libsource (lib "easyedapro") (part "0603WAF1003T5E"))
    )
    (comp (ref "R12")
      (value "100kΩ")
      (footprint "easyedapro:R0603")
      (description "电阻类型:薄膜电阻;阻值:100kΩ;精度:±0.1%;功率:100mW;")
      (fields (field (name "Manufacturer Part") "RT0603BRD07100KL") (field (name "Manufacturer") "YAGEO(国巨)"))
      (libsource (lib "easyedapro") (part "RT0603BRD07100KL"))
    )
    (comp (ref "R13")
      (value "18kΩ")
      (footprint "easyedapro:R0603")
      (description "电阻类型:厚膜电阻;阻值:18kΩ;精度:±1%;功率:100mW;最大工作电压:75V;温度系数:±100ppm/°C;")
      (fields
        (field (name "Manufacturer Part") "0603WAF1802T5E")
        (field (name "Manufacturer") "UNI-ROYAL(厚声)")
      )
      (libsource (lib "easyedapro") (part "0603WAF1802T5E"))
    )
    (comp (ref "R14")
      (value "40.2kΩ")
      (footprint "easyedapro:R0603")
      (description "电阻类型:厚膜电阻;阻值:40.2kΩ;精度:±1%;功率:100mW;")
      (fields
        (field (name "Manufacturer Part") "0603WAF4022T5E")
        (field (name "Manufacturer") "UNI-ROYAL(厚声)")
      )
      (libsource (lib "easyedapro") (part "0603WAF4022T5E"))
    )
    (comp (ref "R15")
      (value "8.87kΩ")
      (footprint "easyedapro:R0603")
      (description "电阻类型:厚膜电阻;阻值:8.87kΩ;精度:±1%;功率:100mW;最大工作电压:75V;温度系数:±100ppm/°C;")
      (fields
        (field (name "Manufacturer Part") "0603WAF8871T5E")
        (field (name "Manufacturer") "UNI-ROYAL(厚声)")
      )
      (libsource (lib "easyedapro") (part "0603WAF8871T5E"))
    )
    (comp (ref "R16")
      (value "7.68kΩ")
      (footprint "easyedapro:R0603")
      (description "电阻类型:厚膜电阻;阻值:13kΩ;精度:±1%;功率:100mW;")
      (fields
        (field (name "Manufacturer Part") "0603WAF1302T5E")
        (field (name "Manufacturer") "UNI-ROYAL(厚声)")
      )
      (libsource (lib "easyedapro") (part "0603WAF1302T5E"))
    )
    (comp (ref "R17")
      (value "100kΩ")
      (footprint "easyedapro:R0603")
      (description "电阻类型:薄膜电阻;阻值:100kΩ;精度:±0.1%;功率:100mW;")
      (fields (field (name "Manufacturer Part") "RT0603BRD07100KL") (field (name "Manufacturer") "YAGEO(国巨)"))
      (libsource (lib "easyedapro") (part "RT0603BRD07100KL"))
    )
    (comp (ref "R18")
      (value "18kΩ")
      (footprint "easyedapro:R0603")
      (description "电阻类型:厚膜电阻;阻值:18kΩ;精度:±1%;功率:100mW;最大工作电压:75V;温度系数:±100ppm/°C;")
      (fields
        (field (name "Manufacturer Part") "0603WAF1802T5E")
        (field (name "Manufacturer") "UNI-ROYAL(厚声)")
      )
      (libsource (lib "easyedapro") (part "0603WAF1802T5E"))
    )
    (comp (ref "R19")
      (value "24.9kΩ")
      (footprint "easyedapro:R0603")
      (description "电阻类型:厚膜电阻;阻值:40.2kΩ;精度:±1%;功率:100mW;")
      (fields
        (field (name "Manufacturer Part") "0603WAF4022T5E")
        (field (name "Manufacturer") "UNI-ROYAL(厚声)")
      )
      (libsource (lib "easyedapro") (part "0603WAF4022T5E"))
    )
    (comp (ref "R20")
      (value "40.2kΩ")
      (footprint "easyedapro:R0603")
      (description "电阻类型:厚膜电阻;阻值:40.2kΩ;精度:±1%;功率:100mW;")
      (fields
        (field (name "Manufacturer Part") "0603WAF4022T5E")
        (field (name "Manufacturer") "UNI-ROYAL(厚声)")
      )
      (libsource (lib "easyedapro") (part "0603WAF4022T5E"))
    )
    (comp (ref "R21")
      (value "0Ω")
      (footprint "easyedapro:R0603")
      (description "电阻类型:厚膜电阻;阻值:0Ω;精度:±1%;功率:100mW;")
      (fields
        (field (name "Manufacturer Part") "0603WAF0000T5E")
        (field (name "Manufacturer") "UNI-ROYAL(厚声)")
      )
      (libsource (lib "easyedapro") (part "0603WAF0000T5E"))
    )
    (comp (ref "R22")
      (value "0Ω")
      (footprint "easyedapro:R0603")
      (description "电阻类型:厚膜电阻;阻值:0Ω;精度:±1%;功率:100mW;")
      (fields
        (field (name "Manufacturer Part") "0603WAF0000T5E")
        (field (name "Manufacturer") "UNI-ROYAL(厚声)")
      )
      (libsource (lib "easyedapro") (part "0603WAF0000T5E"))
    )
    (comp (ref "U1")
      (value "LM358DT")
      (footprint "easyedapro:SOIC-8_L5.0-W4.0-P1.27-LS6.0-BL")
      (description "放大器数:双路;轨到轨:-;增益带宽积(GBP):800kHz;输入失调电压(Vos):7mV;压摆率(SR):0.6V/us;输入偏置电流(Ib):20nA;")
      (fields (field (name "Manufacturer") "ST(意法半导体)"))
      (libsource (lib "easyedapro") (part "LM358DT"))
    )
    (comp (ref "U2")
      (value "MP2225GJ-Z")
      (footprint "easyedapro:TSOT-23-8_L2.9-W1.6-P0.65-LS2.8-BR")
      (description "功能类型:降压型;输出类型:可调;工作电压:4.5V~18V;输出电压:-;输出电流:5A;")
      (fields (field (name "Manufacturer") "MPS(芯源)"))
      (libsource (lib "easyedapro") (part "MP2225GJ-Z"))
    )
    (comp (ref "U3")
      (value "MT1471")
      (footprint "easyedapro:SOT-23-6_L2.9-W1.6-P0.95-LS2.8-BR")
      (fields (field (name "Manufacturer") "西安航天民芯"))
      (libsource (lib "easyedapro") (part "MT1471"))
    )
    (comp (ref "U4")
      (value "INA226AIDGSR")
      (footprint "easyedapro:MSOP-10_L3.0-W3.0-P0.50-LS5.0-BL")
      (description "INA226 支持报警功能的 36V、双向、超高精度、低侧/高侧、I2C 输出电流/功率监控器")
      (fields (field (name "Manufacturer") "TI(德州仪器)"))
      (libsource (lib "easyedapro") (part "INA226AIDGSR"))
    )
    (comp (ref "U5")
      (value "AHT20")
      (footprint "easyedapro:SENSOR-SMD_L3.0-W3.0-P1.00-BR")
      (fields (field (name "Manufacturer") "广州奥松"))
      (libsource (lib "easyedapro") (part "AHT20_C2757850"))
    )
    (comp (ref "CORE1")
      (value "HLK-7621")
      (footprint "easyedapro:COMM-SMD_HLK-7621")
      (description "双核千兆5端口/PCIe接口/OpenWrt开发")
      (fields (field (name "Manufacturer") "HI-LINK(海凌科)"))
      (libsource (lib "easyedapro") (part "HLK-7621_C3029172"))
    )
    (comp (ref "F1")
      (value "BSMD0603-075-6V")
      (footprint "easyedapro:F0603")
      (description "最大电压:6V;最大电流:40A;保持电流:750mA;跳闸电流:1.5A;")
      (fields (field (name "Manufacturer") "BHFUSE(佰宏)"))
      (libsource (lib "easyedapro") (part "BSMD0603-075-6V"))
    )
    (comp (ref "F2")
      (value "BSMD0603-075-6V")
      (footprint "easyedapro:F0603")
      (description "最大电压:6V;最大电流:40A;保持电流:750mA;跳闸电流:1.5A;")
      (fields (field (name "Manufacturer") "BHFUSE(佰宏)"))
      (libsource (lib "easyedapro") (part "BSMD0603-075-6V"))
    )
    (comp (ref "I2C_1")
      (value "PZ254V-11-04P")
      (footprint "easyedapro:HDR-TH_4P-P2.54-V-M")
      (fields (field (name "Manufacturer") "XFCN(兴飞)"))
      (libsource (lib "easyedapro") (part "PZ254V-11-04P_C2691448"))
    )
    (comp (ref "Q4")
      (value "S9013-E")
      (footprint "easyedapro:SOT-23-3_L2.9-W1.3-P1.90-LS2.4-BR")
      (description "晶体管类型:NPN;集电极电流(Ic):500mA;集射极击穿电压(Vceo):25V;功率(Pd):300mW;直流电流增益(hFE@Ic,Vce):120@50mA,1V;")
      (fields (field (name "Manufacturer") "MDD(辰达半导体)"))
      (libsource (lib "easyedapro") (part "S9013-E"))
    )
    (comp (ref "R23")
      (value "4.7kΩ")
      (footprint "easyedapro:R0603")
      (description "电阻类型:厚膜电阻;阻值:4.7kΩ;精度:±1%;功率:100mW;")
      (fields
        (field (name "Manufacturer Part") "0603WAF4701T5E")
        (field (name "Manufacturer") "UNI-ROYAL(厚声)")
      )
      (libsource (lib "easyedapro") (part "0603WAF4701T5E"))
    )
    (comp (ref "R24")
      (value "4.7kΩ")
      (footprint "easyedapro:R0603")
      (description "电阻类型:厚膜电阻;阻值:4.7kΩ;精度:±1%;功率:100mW;")
      (fields
        (field (name "Manufacturer Part") "0603WAF4701T5E")
        (field (name "Manufacturer") "UNI-ROYAL(厚声)")
      )
      (libsource (lib "easyedapro") (part "0603WAF4701T5E"))
    )
    (comp (ref "R25")
      (value "4.7kΩ")
      (footprint "easyedapro:R0603")
      (description "电阻类型:厚膜电阻;阻值:4.7kΩ;精度:±1%;功率:100mW;")
      (fields
        (field (name "Manufacturer Part") "0603WAF4701T5E")
        (field (name "Manufacturer") "UNI-ROYAL(厚声)")
      )
      (libsource (lib "easyedapro") (part "0603WAF4701T5E"))
    )
    (comp (ref "R26")
      (value "10kΩ")
      (footprint "easyedapro:R0603")
      (description "电阻类型:厚膜电阻;阻值:10kΩ;精度:±1%;功率:100mW;")
      (fields
        (field (name "Manufacturer Part") "0603WAF1002T5E")
        (field (name "Manufacturer") "UNI-ROYAL(厚声)")
      )
      (libsource (lib "easyedapro") (part "0603WAF1002T5E"))
    )
    (comp (ref "R27")
      (value "10kΩ")
      (footprint "easyedapro:R0603")
      (description "电阻类型:厚膜电阻;阻值:10kΩ;精度:±1%;功率:100mW;")
      (fields
        (field (name "Manufacturer Part") "0603WAF1002T5E")
        (field (name "Manufacturer") "UNI-ROYAL(厚声)")
      )
      (libsource (lib "easyedapro") (part "0603WAF1002T5E"))
    )
    (comp (ref "R28")
      (value "10kΩ")
      (footprint "easyedapro:R0603")
      (description "电阻类型:厚膜电阻;阻值:10kΩ;精度:±1%;功率:100mW;")
      (fields
        (field (name "Manufacturer Part") "0603WAF1002T5E")
        (field (name "Manufacturer") "UNI-ROYAL(厚声)")
      )
      (libsource (lib "easyedapro") (part "0603WAF1002T5E"))
    )
    (comp (ref "TP1")
      (value "~")
      (footprint "easyedapro:Test-Point-0.5mm")
      (description "Test Point 测试点")
      (libsource (lib "easyedapro") (part "Test-Point"))
    )
    (comp (ref "TP2")
      (value "~")
      (footprint "easyedapro:Test-Point-0.5mm")
      (description "Test Point 测试点")
      (libsource (lib "easyedapro") (part "Test-Point"))
    )
    (comp (ref "TTL1")
      (value "PZ254V-11-04P")
      (footprint "easyedapro:HDR-TH_4P-P2.54-V-M")
      (fields (field (name "Manufacturer") "XFCN(兴飞)"))
      (libsource (lib "easyedapro") (part "PZ254V-11-04P_C2691448"))
    )
    (comp (ref "TTL2")
      (value "HX PZ2.0-1x4P ZZ")
      (footprint "easyedapro:HDR-TH_4P-P2.00-V-M-3")
      (fields (field (name "Manufacturer") "hanxia(韩下)"))
      (libsource (lib "easyedapro") (part "HX PZ2.0-1X4P ZZ"))
    )
    (comp (ref "C22")
      (value "22uF")
      (fields
        (field (name "Manufacturer Part") "CC0805MKX5R7BB226")
        (field (name "Manufacturer") "YAGEO(国巨)")
      )
      (libsource (lib "easyedapro") (part "cl21a226maqnnne"))
    )
    (comp (ref "C23")
      (value "22uF")
      (fields
        (field (name "Manufacturer Part") "CC0805MKX5R7BB226")
        (field (name "Manufacturer") "YAGEO(国巨)")
      )
      (libsource (lib "easyedapro") (part "cl21a226maqnnne"))
    )
    (comp (ref "PCIE1")
      (value "Mini-PCI-E_Socket_5V")
      (libsource (lib "easyedapro") (part "Mini-PCI-E_Socket_5V"))
    )
    (comp (ref "PCIE2")
      (value "Mini-PCI-E_Socket_5V")
      (libsource (lib "easyedapro") (part "Mini-PCI-E_Socket_5V"))
    )
    (comp (ref "R29")
      (value "0Ω")
      (footprint "easyedapro:R0603")
      (description "电阻类型:厚膜电阻;阻值:0Ω;精度:±1%;功率:100mW;")
      (fields
        (field (name "Manufacturer Part") "0603WAF0000T5E")
        (field (name "Manufacturer") "UNI-ROYAL(厚声)")
      )
      (libsource (lib "easyedapro") (part "0603WAF0000T5E"))
    )
    (comp (ref "R30")
      (value "0Ω")
      (footprint "easyedapro:R0603")
      (description "电阻类型:厚膜电阻;阻值:0Ω;精度:±1%;功率:100mW;")
      (fields
        (field (name "Manufacturer Part") "0603WAF0000T5E")
        (field (name "Manufacturer") "UNI-ROYAL(厚声)")
      )
      (libsource (lib "easyedapro") (part "0603WAF0000T5E"))
    )
    (comp (ref "R31")
      (value "0Ω")
      (footprint "easyedapro:R0603")
      (description "电阻类型:厚膜电阻;阻值:0Ω;精度:±1%;功率:100mW;")
      (fields
        (field (name "Manufacturer Part") "0603WAF0000T5E")
        (field (name "Manufacturer") "UNI-ROYAL(厚声)")
      )
      (libsource (lib "easyedapro") (part "0603WAF0000T5E"))
    )
    (comp (ref "R32")
      (value "0Ω")
      (footprint "easyedapro:R0603")
      (description "电阻类型:厚膜电阻;阻值:0Ω;精度:±1%;功率:100mW;")
      (fields
        (field (name "Manufacturer Part") "0603WAF0000T5E")
        (field (name "Manufacturer") "UNI-ROYAL(厚声)")
      )
      (libsource (lib "easyedapro") (part "0603WAF0000T5E"))
    )
    (comp (ref "R33")
      (value "0Ω")
      (footprint "easyedapro:R0603")
      (description "电阻类型:厚膜电阻;阻值:0Ω;精度:±1%;功率:100mW;")
      (fields
        (field (name "Manufacturer Part") "0603WAF0000T5E")
        (field (name "Manufacturer") "UNI-ROYAL(厚声)")
      )
      (libsource (lib "easyedapro") (part "0603WAF0000T5E"))
    )
    (comp (ref "R34")
      (value "0Ω")
      (footprint "easyedapro:R0603")
      (description "电阻类型:厚膜电阻;阻值:0Ω;精度:±1%;功率:100mW;")
      (fields
        (field (name "Manufacturer Part") "0603WAF0000T5E")
        (field (name "Manufacturer") "UNI-ROYAL(厚声)")
      )
      (libsource (lib "easyedapro") (part "0603WAF0000T5E"))
    )
    (comp (ref "C24")
      (value "22uF")
      (fields
        (field (name "Manufacturer Part") "CC0805MKX5R7BB226")
        (field (name "Manufacturer") "YAGEO(国巨)")
      )
      (libsource (lib "easyedapro") (part "cl21a226maqnnne"))
    )
    (comp (ref "C25")
      (value "100nF")
      (fields
        (field (name "Manufacturer Part") "CL10B104KA8NNNC")
        (field (name "Manufacturer") "SAMSUNG(三星)")
      )
      (libsource (lib "easyedapro") (part "0603B104K500NT"))
    )
    (comp (ref "C26")
      (value "33pF")
      (footprint "easyedapro:C0603")
      (description "容值:33pF;精度:±5%;额定电压:50V;材质(温度系数):C0G;")
      (fields (field (name "Manufacturer Part") "0603CG330J500NT") (field (name "Manufacturer") "FH(风华)"))
      (libsource (lib "easyedapro") (part "0603CG330J500NT"))
    )
    (comp (ref "C27")
      (value "33pF")
      (footprint "easyedapro:C0603")
      (description "容值:33pF;精度:±5%;额定电压:50V;材质(温度系数):C0G;")
      (fields (field (name "Manufacturer Part") "0603CG330J500NT") (field (name "Manufacturer") "FH(风华)"))
      (libsource (lib "easyedapro") (part "0603CG330J500NT"))
    )
    (comp (ref "C28")
      (value "33pF")
      (footprint "easyedapro:C0603")
      (description "容值:33pF;精度:±5%;额定电压:50V;材质(温度系数):C0G;")
      (fields (field (name "Manufacturer Part") "0603CG330J500NT") (field (name "Manufacturer") "FH(风华)"))
      (libsource (lib "easyedapro") (part "0603CG330J500NT"))
    )
    (comp (ref "F3")
      (value "BSMD0603-075-6V")
      (footprint "easyedapro:F0603")
      (description "最大电压:6V;最大电流:40A;保持电流:750mA;跳闸电流:1.5A;")
      (fields (field (name "Manufacturer") "BHFUSE(佰宏)"))
      (libsource (lib "easyedapro") (part "BSMD0603-075-6V"))
    )
    (comp (ref "L3")
      (value "ACM2012-900-2P-T001")
      (footprint "easyedapro:FILTER-SMD_4P-L2.0-W1.2-TL_ACM2012E")
      (description "线路数:2;阻抗 @ 频率:90Ω@100MHz;直流电阻(DCR):190mΩ;")
      (fields (field (name "Manufacturer") "TDK"))
      (libsource (lib "easyedapro") (part "ACM2012-900-2P-T001"))
    )
    (comp (ref "R35")
      (value "10kΩ")
      (footprint "easyedapro:R0603")
      (description "电阻类型:厚膜电阻;阻值:10kΩ;精度:±1%;功率:100mW;")
      (fields
        (field (name "Manufacturer Part") "0603WAF1002T5E")
        (field (name "Manufacturer") "UNI-ROYAL(厚声)")
      )
      (libsource (lib "easyedapro") (part "0603WAF1002T5E"))
    )
    (comp (ref "R36")
      (value "0Ω")
      (footprint "easyedapro:R0603")
      (description "电阻类型:厚膜电阻;阻值:0Ω;精度:±1%;功率:100mW;")
      (fields
        (field (name "Manufacturer Part") "0603WAF0000T5E")
        (field (name "Manufacturer") "UNI-ROYAL(厚声)")
      )
      (libsource (lib "easyedapro") (part "0603WAF0000T5E"))
    )
    (comp (ref "R37")
      (value "15kΩ")
      (footprint "easyedapro:R0603")
      (description "电阻类型:厚膜电阻;阻值:15kΩ;精度:±1%;功率:100mW;")
      (fields (field (name "Manufacturer Part") "AC0603FR-0715KL") (field (name "Manufacturer") "YAGEO(国巨)"))
      (libsource (lib "easyedapro") (part "AC0603FR-0715KL"))
    )
    (comp (ref "R38")
      (value "not install")
      (footprint "easyedapro:R0603")
      (description "电阻类型:厚膜电阻;阻值:33kΩ;精度:±1%;功率:100mW;")
      (fields (field (name "Manufacturer Part") "RC0603FR-0733KL") (field (name "Manufacturer") "YAGEO(国巨)"))
      (libsource (lib "easyedapro") (part "RC0603FR-0733KL"))
    )
    (comp (ref "SIM1")
      (value "SNO-1350")
      (footprint "easyedapro:SIM-SMD_SNO-1350")
      (description "触头材质:-;卡连接方式:-;触头镀层:-;连接器类型:-;卡类型:-;")
      (fields (field (name "Manufacturer") "HANBO(汉博)"))
      (libsource (lib "easyedapro") (part "SNO-1350"))
    )
    (comp (ref "U6")
      (value "USBLC6-4SC6")
      (footprint "easyedapro:SOT-23-6_L2.9-W1.6-P0.95-LS2.8-BL")
      (fields (field (name "Manufacturer") "TECH PUBLIC(台舟)"))
      (libsource (lib "easyedapro") (part "USBLC6-4SC6_C5197386"))
    )
    (comp (ref "U7")
      (value "USBLC6-4SC6")
      (footprint "easyedapro:SOT-23-6_L2.9-W1.6-P0.95-LS2.8-BL")
      (fields (field (name "Manufacturer") "TECH PUBLIC(台舟)"))
      (libsource (lib "easyedapro") (part "USBLC6-4SC6_C5197386"))
    )
    (comp (ref "USB1")
      (value "BX-XH2.54-4PZZ")
      (footprint "easyedapro:CONN-TH_4P-P2.50_BX-XH2.54-4PZZ")
      (fields (field (name "Manufacturer") "Bossie(博锡)"))
      (libsource (lib "easyedapro") (part "BX-XH2.54-4PZZ"))
    )
    (comp (ref "WWAN1")
      (value "~")
      (footprint "easyedapro:NGFF_B_SOCKET")
      (libsource (lib "easyedapro") (part "NGFF_B_KEY_H3.2"))
    )
    (comp (ref "C29")
      (value "1nF")
      (footprint "easyedapro:C0603")
      (description "容值:1nF;精度:±10%;额定电压:50V;材质(温度系数):X7R;")
      (fields
        (field (name "Manufacturer Part") "CL10B102KB8NNNC")
        (field (name "Manufacturer") "SAMSUNG(三星)")
      )
      (libsource (lib "easyedapro") (part "CL10B102KB8NNNC"))
    )
    (comp (ref "C30")
      (value "1nF")
      (footprint "easyedapro:C0603")
      (description "容值:1nF;精度:±10%;额定电压:50V;材质(温度系数):X7R;")
      (fields
        (field (name "Manufacturer Part") "CL10B102KB8NNNC")
        (field (name "Manufacturer") "SAMSUNG(三星)")
      )
      (libsource (lib "easyedapro") (part "CL10B102KB8NNNC"))
    )
    (comp (ref "C31")
      (value "1nF")
      (footprint "easyedapro:C0603")
      (description "容值:1nF;精度:±10%;额定电压:50V;材质(温度系数):X7R;")
      (fields
        (field (name "Manufacturer Part") "CL10B102KB8NNNC")
        (field (name "Manufacturer") "SAMSUNG(三星)")
      )
      (libsource (lib "easyedapro") (part "CL10B102KB8NNNC"))
    )
    (comp (ref "GE_LAN1")
      (value "HR911130A")
      (footprint "easyedapro:RJ45-TH_HR911130A")
      (description "连接器类型:RJ45插座;端口数量:1;屏蔽:-;LED:带LED;等级:-;")
      (fields (field (name "Manufacturer") "HANRUN(汉仁)"))
      (libsource (lib "easyedapro") (part "HR911130A"))
    )
    (comp (ref "GE_LAN2")
      (value "HR911130A")
      (footprint "easyedapro:RJ45-TH_HR911130A")
      (description "连接器类型:RJ45插座;端口数量:1;屏蔽:-;LED:带LED;等级:-;")
      (fields (field (name "Manufacturer") "HANRUN(汉仁)"))
      (libsource (lib "easyedapro") (part "HR911130A"))
    )
    (comp (ref "GE_WAN")
      (value "HR911130A")
      (footprint "easyedapro:RJ45-TH_HR911130A")
      (description "连接器类型:RJ45插座;端口数量:1;屏蔽:-;LED:带LED;等级:-;")
      (fields (field (name "Manufacturer") "HANRUN(汉仁)"))
      (libsource (lib "easyedapro") (part "HR911130A"))
    )
    (comp (ref "R39")
      (value "1kΩ")
      (footprint "easyedapro:R0603")
      (description "电阻类型:厚膜电阻;阻值:1kΩ;精度:±1%;功率:100mW;最大工作电压:75V;温度系数:±100ppm/°C;")
      (fields
        (field (name "Manufacturer Part") "0603WAF1001T5E")
        (field (name "Manufacturer") "UNI-ROYAL(厚声)")
      )
      (libsource (lib "easyedapro") (part "0603WAF1001T5E"))
    )
    (comp (ref "R40")
      (value "1kΩ")
      (footprint "easyedapro:R0603")
      (description "电阻类型:厚膜电阻;阻值:200Ω;精度:±1%;功率:100mW;最大工作电压:75V;温度系数:±100ppm/°C;")
      (fields
        (field (name "Manufacturer Part") "0603WAF1001T5E")
        (field (name "Manufacturer") "UNI-ROYAL(厚声)")
      )
      (libsource (lib "easyedapro") (part "0603WAF2000T5E"))
    )
    (comp (ref "R41")
      (value "1kΩ")
      (footprint "easyedapro:R0603")
      (description "电阻类型:厚膜电阻;阻值:1kΩ;精度:±1%;功率:100mW;最大工作电压:75V;温度系数:±100ppm/°C;")
      (fields
        (field (name "Manufacturer Part") "0603WAF1001T5E")
        (field (name "Manufacturer") "UNI-ROYAL(厚声)")
      )
      (libsource (lib "easyedapro") (part "0603WAF1001T5E"))
    )
    (comp (ref "R42")
      (value "1kΩ")
      (footprint "easyedapro:R0603")
      (description "电阻类型:厚膜电阻;阻值:200Ω;精度:±1%;功率:100mW;最大工作电压:75V;温度系数:±100ppm/°C;")
      (fields
        (field (name "Manufacturer Part") "0603WAF1001T5E")
        (field (name "Manufacturer") "UNI-ROYAL(厚声)")
      )
      (libsource (lib "easyedapro") (part "0603WAF2000T5E"))
    )
    (comp (ref "R43")
      (value "1kΩ")
      (footprint "easyedapro:R0603")
      (description "电阻类型:厚膜电阻;阻值:1kΩ;精度:±1%;功率:100mW;最大工作电压:75V;温度系数:±100ppm/°C;")
      (fields
        (field (name "Manufacturer Part") "0603WAF1001T5E")
        (field (name "Manufacturer") "UNI-ROYAL(厚声)")
      )
      (libsource (lib "easyedapro") (part "0603WAF1001T5E"))
    )
    (comp (ref "R44")
      (value "1kΩ")
      (footprint "easyedapro:R0603")
      (description "电阻类型:厚膜电阻;阻值:200Ω;精度:±1%;功率:100mW;最大工作电压:75V;温度系数:±100ppm/°C;")
      (fields
        (field (name "Manufacturer Part") "0603WAF1001T5E")
        (field (name "Manufacturer") "UNI-ROYAL(厚声)")
      )
      (libsource (lib "easyedapro") (part "0603WAF2000T5E"))
    )
  )
  (nets
    (net (code "1") (name "3.3V") (class "Default")
      (node (ref "C10") (pin "1") (pinfunction "1_1") (pintype "input"))
      (node (ref "C11") (pin "1") (pinfunction "1_1") (pintype "input"))
      (node (ref "C12") (pin "1") (pinfunction "1_1") (pintype "input"))
      (node (ref "C13") (pin "1") (pinfunction "1_1") (pintype "input"))
      (node (ref "C22") (pin "1") (pinfunction "1_1") (pintype "input"))
      (node (ref "C23") (pin "1") (pinfunction "1_1") (pintype "input"))
      (node (ref "C24") (pin "1") (pinfunction "1_1") (pintype "input"))
      (node (ref "CORE1") (pin "1") (pinfunction "3.3VD_1") (pintype "unspecified"))
      (node (ref "CORE1") (pin "2") (pinfunction "3.3VD_2") (pintype "unspecified"))
      (node (ref "CORE1") (pin "3") (pinfunction "3.3VD_3") (pintype "unspecified"))
      (node (ref "CORE1") (pin "4") (pinfunction "3.3VD_4") (pintype "unspecified"))
      (node (ref "D9") (pin "1") (pinfunction "1_1") (pintype "unspecified"))
      (node (ref "F1") (pin "1") (pinfunction "1_1") (pintype "unspecified"))
      (node (ref "F2") (pin "1") (pinfunction "1_1") (pintype "unspecified"))
      (node (ref "GE_LAN1") (pin "11") (pinfunction "11_11") (pintype "unspecified"))
      (node (ref "GE_LAN1") (pin "14") (pinfunction "14_14") (pintype "unspecified"))
      (node (ref "GE_LAN2") (pin "11") (pinfunction "11_11") (pintype "unspecified"))
      (node (ref "GE_LAN2") (pin "14") (pinfunction "14_14") (pintype "unspecified"))
      (node (ref "GE_WAN") (pin "11") (pinfunction "11_11") (pintype "unspecified"))
      (node (ref "GE_WAN") (pin "14") (pinfunction "14_14") (pintype "unspecified"))
      (node (ref "L1") (pin "2") (pinfunction "2_2") (pintype "unspecified"))
      (node (ref "PCIE1") (pin "2") (pinfunction "+3.3Vaux_2") (pintype "input"))
      (node (ref "PCIE1") (pin "24") (pinfunction "+3.3Vaux_24") (pintype "input"))
      (node (ref "PCIE1") (pin "52") (pinfunction "+3.3Vaux_52") (pintype "input"))
      (node (ref "PCIE2") (pin "2") (pinfunction "+3.3Vaux_2") (pintype "input"))
      (node (ref "PCIE2") (pin "24") (pinfunction "+3.3Vaux_24") (pintype "input"))
      (node (ref "PCIE2") (pin "52") (pinfunction "+3.3Vaux_52") (pintype "input"))
      (node (ref "R14") (pin "1") (pinfunction "1_1") (pintype "input"))
      (node (ref "R22") (pin "2") (pinfunction "2_2") (pintype "input"))
      (node (ref "R24") (pin "2") (pinfunction "2_2") (pintype "input"))
      (node (ref "R25") (pin "2") (pinfunction "2_2") (pintype "input"))
      (node (ref "R27") (pin "2") (pinfunction "2_2") (pintype "input"))
      (node (ref "R28") (pin "2") (pinfunction "2_2") (pintype "input"))
      (node (ref "R35") (pin "1") (pinfunction "1_1") (pintype "input"))
      (node (ref "TTL1") (pin "1") (pinfunction "1_1") (pintype "unspecified"))
      (node (ref "WWAN1") (pin "2") (pinfunction "3.3V_2") (pintype "input"))
      (node (ref "WWAN1") (pin "4") (pinfunction "3.3V_4") (pintype "input"))
      (node (ref "WWAN1") (pin "70") (pinfunction "3.3V_70") (pintype "input"))
      (node (ref "WWAN1") (pin "72") (pinfunction "3.3V_72") (pintype "input"))
      (node (ref "WWAN1") (pin "74") (pinfunction "3.3V_74") (pintype "input"))
    )
    (net (code "2") (name "5V") (class "Default")
      (node (ref "C16") (pin "1") (pinfunction "1_1") (pintype "input"))
      (node (ref "C17") (pin "2") (pinfunction "2_2") (pintype "input"))
      (node (ref "C19") (pin "1") (pinfunction "1_1") (pintype "input"))
      (node (ref "D10") (pin "1") (pinfunction "K_1") (pintype "unspecified"))
      (node (ref "F3") (pin "1") (pinfunction "1_1") (pintype "unspecified"))
      (node (ref "L2") (pin "2") (pinfunction "2_2") (pintype "unspecified"))
      (node (ref "R20") (pin "2") (pinfunction "2_2") (pintype "input"))
      (node (ref "R29") (pin "1") (pinfunction "1_1") (pintype "input"))
      (node (ref "R30") (pin "1") (pinfunction "1_1") (pintype "input"))
      (node (ref "R32") (pin "1") (pinfunction "1_1") (pintype "input"))
      (node (ref "R33") (pin "1") (pinfunction "1_1") (pintype "input"))
    )
    (net (code "3") (name "12V") (class "Default")
      (node (ref "C18") (pin "1") (pinfunction "1_1") (pintype "input"))
      (node (ref "C20") (pin "1") (pinfunction "1_1") (pintype "input"))
      (node (ref "C3") (pin "1") (pinfunction "1_1") (pintype "input"))
      (node (ref "C7") (pin "1") (pinfunction "1_1") (pintype "input"))
      (node (ref "C8") (pin "1") (pinfunction "1_1") (pintype "input"))
      (node (ref "D4") (pin "1") (pinfunction "C_1") (pintype "unspecified"))
      (node (ref "D8") (pin "2") (pinfunction "A_2") (pintype "unspecified"))
      (node (ref "FH1") (pin "2") (pinfunction "2_2") (pintype "input"))
      (node (ref "Q3") (pin "2") (pinfunction "D_2") (pintype "unspecified"))
      (node (ref "R12") (pin "2") (pinfunction "2_2") (pintype "input"))
      (node (ref "R17") (pin "1") (pinfunction "1_1") (pintype "input"))
      (node (ref "R2") (pin "1") (pinfunction "1_1") (pintype "input"))
      (node (ref "U2") (pin "2") (pinfunction "IN_2") (pintype "unspecified"))
      (node (ref "U3") (pin "3") (pinfunction "VIN_3") (pintype "input"))
    )
    (net (code "4") (name "12V_SIG") (class "Default")
      (node (ref "C1") (pin "1") (pinfunction "1_1") (pintype "input"))
      (node (ref "D1") (pin "1") (pinfunction "K_1") (pintype "unspecified"))
      (node (ref "R5") (pin "1") (pinfunction "1_1") (pintype "unspecified"))
    )
    (net (code "5") (name "CAR_12VIN") (class "Default")
      (node (ref "C2") (pin "1") (pinfunction "1_1") (pintype "input"))
      (node (ref "D2") (pin "2") (pinfunction "K_2") (pintype "unspecified"))
      (node (ref "D3") (pin "1") (pinfunction "C_1") (pintype "unspecified"))
      (node (ref "Q3") (pin "3") (pinfunction "S_3") (pintype "unspecified"))
      (node (ref "R11") (pin "1") (pinfunction "1_1") (pintype "input"))
      (node (ref "R4") (pin "1") (pinfunction "1_1") (pintype "input"))
      (node (ref "U1") (pin "8") (pinfunction "V+_8") (pintype "unspecified"))
    )
    (net (code "6") (name "CAR_ACC") (class "Default")
      (node (ref "C4") (pin "2") (pinfunction "2_2") (pintype "input"))
      (node (ref "D5") (pin "1") (pinfunction "K_1") (pintype "unspecified"))
      (node (ref "D6") (pin "1") (pinfunction "C_1") (pintype "unspecified"))
      (node (ref "R26") (pin "1") (pinfunction "1_1") (pintype "input"))
      (node (ref "R3") (pin "2") (pinfunction "2_2") (pintype "input"))
      (node (ref "R8") (pin "1") (pinfunction "1_1") (pintype "input"))
    )
    (net (code "7") (name "ESW_P0_A_TXV+") (class "Default")
      (node (ref "CORE1") (pin "28") (pinfunction "ESW_TXVP_A_P0_28") (pintype "unspecified"))
    )
    (net (code "8") (name "ESW_P0_A_TXV-") (class "Default")
      (node (ref "CORE1") (pin "29") (pinfunction "ESW_TXVN_A_P0_29") (pintype "unspecified"))
    )
    (net (code "9") (name "ESW_P0_B_TXV+") (class "Default")
      (node (ref "CORE1") (pin "30") (pinfunction "ESW_TXVP_B_P0_30") (pintype "unspecified"))
    )
    (net (code "10") (name "ESW_P0_B_TXV-") (class "Default")
      (node (ref "CORE1") (pin "31") (pinfunction "ESW_TXVN_B_P0_31") (pintype "unspecified"))
    )
    (net (code "11") (name "ESW_P0_C_TXV+") (class "Default")
      (node (ref "CORE1") (pin "32") (pinfunction "ESW_TXVP_C_P0_32") (pintype "unspecified"))
    )
    (net (code "12") (name "ESW_P0_C_TXV-") (class "Default")
      (node (ref "CORE1") (pin "33") (pinfunction "ESW_TXVN_C_P0_33") (pintype "unspecified"))
    )
    (net (code "13") (name "ESW_P0_D_TXV+") (class "Default")
      (node (ref "CORE1") (pin "34") (pinfunction "ESW_TXVP_D_P0_34") (pintype "unspecified"))
    )
    (net (code "14") (name "ESW_P0_D_TXV-") (class "Default")
      (node (ref "CORE1") (pin "35") (pinfunction "ESW_TXVN_D_P0_35") (pintype "unspecified"))
    )
    (net (code "15") (name "ESW_P1_A_TXV+") (class "Default")
      (node (ref "CORE1") (pin "36") (pinfunction "ESW_TXVP_A_P1_36") (pintype "unspecified"))
      (node (ref "GE_LAN1") (pin "P2") (pinfunction "MDI0+_P2") (pintype "unspecified"))
    )
    (net (code "16") (name "ESW_P1_A_TXV-") (class "Default")
      (node (ref "CORE1") (pin "37") (pinfunction "ESW_TXVN_A_P1_37") (pintype "unspecified"))
      (node (ref "GE_LAN1") (pin "P3") (pinfunction "MDI0-_P3") (pintype "unspecified"))
    )
    (net (code "17") (name "ESW_P1_B_TXV+") (class "Default")
      (node (ref "CORE1") (pin "38") (pinfunction "ESW_TXVP_B_P1_38") (pintype "unspecified"))
      (node (ref "GE_LAN1") (pin "P4") (pinfunction "MDI1+_P4") (pintype "unspecified"))
    )
    (net (code "18") (name "ESW_P1_B_TXV-") (class "Default")
      (node (ref "CORE1") (pin "39") (pinfunction "ESW_TXVN_B_P1_39") (pintype "unspecified"))
      (node (ref "GE_LAN1") (pin "P7") (pinfunction "MDI1-_P7") (pintype "unspecified"))
    )
    (net (code "19") (name "ESW_P1_C_TXV+") (class "Default")
      (node (ref "CORE1") (pin "40") (pinfunction "ESW_TXVP_C_P1_40") (pintype "unspecified"))
      (node (ref "GE_LAN1") (pin "P5") (pinfunction "MDI2+_P5") (pintype "unspecified"))
    )
    (net (code "20") (name "ESW_P1_C_TXV-") (class "Default")
      (node (ref "CORE1") (pin "41") (pinfunction "ESW_TXVN_C_P1_41") (pintype "unspecified"))
      (node (ref "GE_LAN1") (pin "P6") (pinfunction "MDI2-_P6") (pintype "unspecified"))
    )
    (net (code "21") (name "ESW_P1_D_TXV+") (class "Default")
      (node (ref "CORE1") (pin "42") (pinfunction "ESW_TXVP_D_P1_42") (pintype "unspecified"))
      (node (ref "GE_LAN1") (pin "P8") (pinfunction "MDI3+_P8") (pintype "unspecified"))
    )
    (net (code "22") (name "ESW_P1_D_TXV-") (class "Default")
      (node (ref "CORE1") (pin "43") (pinfunction "ESW_TXVN_D_P1_43") (pintype "unspecified"))
      (node (ref "GE_LAN1") (pin "P9") (pinfunction "MDI3-_P9") (pintype "unspecified"))
    )
    (net (code "23") (name "ESW_P2_A_TXV+") (class "Default")
      (node (ref "CORE1") (pin "45") (pinfunction "ESW_TXVP_A_P2_45") (pintype "unspecified"))
      (node (ref "GE_LAN2") (pin "P2") (pinfunction "MDI0+_P2") (pintype "unspecified"))
    )
    (net (code "24") (name "ESW_P2_A_TXV-") (class "Default")
      (node (ref "CORE1") (pin "46") (pinfunction "ESW_TXVN_A_P2_46") (pintype "unspecified"))
      (node (ref "GE_LAN2") (pin "P3") (pinfunction "MDI0-_P3") (pintype "unspecified"))
    )
    (net (code "25") (name "ESW_P2_B_TXV+") (class "Default")
      (node (ref "CORE1") (pin "47") (pinfunction "ESW_TXVP_B_P2_47") (pintype "unspecified"))
      (node (ref "GE_LAN2") (pin "P4") (pinfunction "MDI1+_P4") (pintype "unspecified"))
    )
    (net (code "26") (name "ESW_P2_B_TXV-") (class "Default")
      (node (ref "CORE1") (pin "48") (pinfunction "ESW_TXVN_B_P2_48") (pintype "unspecified"))
      (node (ref "GE_LAN2") (pin "P7") (pinfunction "MDI1-_P7") (pintype "unspecified"))
    )
    (net (code "27") (name "ESW_P2_C_TXV+") (class "Default")
      (node (ref "CORE1") (pin "49") (pinfunction "ESW_TXVP_C_P2_49") (pintype "unspecified"))
      (node (ref "GE_LAN2") (pin "P5") (pinfunction "MDI2+_P5") (pintype "unspecified"))
    )
    (net (code "28") (name "ESW_P2_C_TXV-") (class "Default")
      (node (ref "CORE1") (pin "50") (pinfunction "ESW_TXVN_C_P2_50") (pintype "unspecified"))
      (node (ref "GE_LAN2") (pin "P6") (pinfunction "MDI2-_P6") (pintype "unspecified"))
    )
    (net (code "29") (name "ESW_P2_D_TXV+") (class "Default")
      (node (ref "CORE1") (pin "51") (pinfunction "ESW_TXVP_D_P2_51") (pintype "unspecified"))
      (node (ref "GE_LAN2") (pin "P8") (pinfunction "MDI3+_P8") (pintype "unspecified"))
    )
    (net (code "30") (name "ESW_P2_D_TXV-") (class "Default")
      (node (ref "CORE1") (pin "52") (pinfunction "ESW_TXVN_D_P2_52") (pintype "unspecified"))
      (node (ref "GE_LAN2") (pin "P9") (pinfunction "MDI3-_P9") (pintype "unspecified"))
    )
    (net (code "31") (name "ESW_P3_A_TXV+") (class "Default")
      (node (ref "CORE1") (pin "54") (pinfunction "ESW_TXVP_A_P3_54") (pintype "unspecified"))
    )
    (net (code "32") (name "ESW_P3_A_TXV-") (class "Default")
      (node (ref "CORE1") (pin "55") (pinfunction "ESW_TXVN_A_P3_55") (pintype "unspecified"))
    )
    (net (code "33") (name "ESW_P3_B_TXV+") (class "Default")
      (node (ref "CORE1") (pin "56") (pinfunction "ESW_TXVP_B_P3_56") (pintype "unspecified"))
    )
    (net (code "34") (name "ESW_P3_B_TXV-") (class "Default")
      (node (ref "CORE1") (pin "57") (pinfunction "ESW_TXVN_B_P3_57") (pintype "unspecified"))
    )
    (net (code "35") (name "ESW_P3_C_TXV+") (class "Default")
      (node (ref "CORE1") (pin "58") (pinfunction "ESW_TXVP_C_P3_58") (pintype "unspecified"))
    )
    (net (code "36") (name "ESW_P3_C_TXV-") (class "Default")
      (node (ref "CORE1") (pin "59") (pinfunction "ESW_TXVN_C_P3_59") (pintype "unspecified"))
    )
    (net (code "37") (name "ESW_P3_D_TXV+") (class "Default")
      (node (ref "CORE1") (pin "60") (pinfunction "ESW_TXVP_D_P3_60") (pintype "unspecified"))
    )
    (net (code "38") (name "ESW_P3_D_TXV-") (class "Default")
      (node (ref "CORE1") (pin "61") (pinfunction "ESW_TXVN_D_P3_61") (pintype "unspecified"))
    )
    (net (code "39") (name "ESW_P4_A_TXV+") (class "Default")
      (node (ref "CORE1") (pin "63") (pinfunction "ESW_TXVP_A_P4_63") (pintype "unspecified"))
      (node (ref "GE_WAN") (pin "P2") (pinfunction "MDI0+_P2") (pintype "unspecified"))
    )
    (net (code "40") (name "ESW_P4_A_TXV-") (class "Default")
      (node (ref "CORE1") (pin "64") (pinfunction "ESW_TXVN_A_P4_64") (pintype "unspecified"))
      (node (ref "GE_WAN") (pin "P3") (pinfunction "MDI0-_P3") (pintype "unspecified"))
    )
    (net (code "41") (name "ESW_P4_B_TXV+") (class "Default")
      (node (ref "CORE1") (pin "65") (pinfunction "ESW_TXVP_B_P4_65") (pintype "unspecified"))
      (node (ref "GE_WAN") (pin "P4") (pinfunction "MDI1+_P4") (pintype "unspecified"))
    )
    (net (code "42") (name "ESW_P4_B_TXV-") (class "Default")
      (node (ref "CORE1") (pin "66") (pinfunction "ESW_TXVN_B_P4_66") (pintype "unspecified"))
      (node (ref "GE_WAN") (pin "P7") (pinfunction "MDI1-_P7") (pintype "unspecified"))
    )
    (net (code "43") (name "ESW_P4_C_TXV+") (class "Default")
      (node (ref "CORE1") (pin "67") (pinfunction "ESW_TXVP_C_P4_67") (pintype "unspecified"))
      (node (ref "GE_WAN") (pin "P5") (pinfunction "MDI2+_P5") (pintype "unspecified"))
    )
    (net (code "44") (name "ESW_P4_C_TXV-") (class "Default")
      (node (ref "CORE1") (pin "68") (pinfunction "ESW_TXVN_C_P4_68") (pintype "unspecified"))
      (node (ref "GE_WAN") (pin "P6") (pinfunction "MDI2-_P6") (pintype "unspecified"))
    )
    (net (code "45") (name "ESW_P4_D_TXV+") (class "Default")
      (node (ref "CORE1") (pin "69") (pinfunction "ESW_TXVP_D_P4_69") (pintype "unspecified"))
      (node (ref "GE_WAN") (pin "P8") (pinfunction "MDI3+_P8") (pintype "unspecified"))
    )
    (net (code "46") (name "ESW_P4_D_TXV-") (class "Default")
      (node (ref "CORE1") (pin "70") (pinfunction "ESW_TXVN_D_P4_70") (pintype "unspecified"))
      (node (ref "GE_WAN") (pin "P9") (pinfunction "MDI3-_P9") (pintype "unspecified"))
    )
    (net (code "47") (name "GND") (class "Default")
      (node (ref "12VOUT1") (pin "2") (pinfunction "2_2") (pintype "unspecified"))
      (node (ref "C1") (pin "2") (pinfunction "2_2") (pintype "input"))
      (node (ref "C10") (pin "2") (pinfunction "2_2") (pintype "input"))
      (node (ref "C11") (pin "2") (pinfunction "2_2") (pintype "input"))
      (node (ref "C12") (pin "2") (pinfunction "2_2") (pintype "input"))
      (node (ref "C14") (pin "1") (pinfunction "1_1") (pintype "unspecified"))
      (node (ref "C16") (pin "2") (pinfunction "2_2") (pintype "input"))
      (node (ref "C17") (pin "1") (pinfunction "1_1") (pintype "input"))
      (node (ref "C18") (pin "2") (pinfunction "2_2") (pintype "input"))
      (node (ref "C19") (pin "2") (pinfunction "2_2") (pintype "input"))
      (node (ref "C2") (pin "2") (pinfunction "2_2") (pintype "input"))
      (node (ref "C20") (pin "2") (pinfunction "2_2") (pintype "input"))
      (node (ref "C21") (pin "2") (pinfunction "2_2") (pintype "input"))
      (node (ref "C22") (pin "2") (pinfunction "2_2") (pintype "input"))
      (node (ref "C23") (pin "2") (pinfunction "2_2") (pintype "input"))
      (node (ref "C24") (pin "2") (pinfunction "2_2") (pintype "input"))
      (node (ref "C25") (pin "2") (pinfunction "2_2") (pintype "input"))
      (node (ref "C26") (pin "1") (pinfunction "1_1") (pintype "input"))
      (node (ref "C27") (pin "2") (pinfunction "2_2") (pintype "input"))
      (node (ref "C28") (pin "2") (pinfunction "2_2") (pintype "input"))
      (node (ref "C29") (pin "2") (pinfunction "2_2") (pintype "input"))
      (node (ref "C3") (pin "2") (pinfunction "2_2") (pintype "input"))
      (node (ref "C30") (pin "2") (pinfunction "2_2") (pintype "input"))
      (node (ref "C31") (pin "2") (pinfunction "2_2") (pintype "input"))
      (node (ref "C4") (pin "1") (pinfunction "1_1") (pintype "input"))
      (node (ref "C5") (pin "1") (pinfunction "1_1") (pintype "input"))
      (node (ref "C6") (pin "1") (pinfunction "1_1") (pintype "input"))
      (node (ref "C7") (pin "2") (pinfunction "2_2") (pintype "input"))
      (node (ref "C8") (pin "2") (pinfunction "2_2") (pintype "input"))
      (node (ref "CAR_IN") (pin "3") (pinfunction "3_3") (pintype "unspecified"))
      (node (ref "CORE1") (pin "119") (pinfunction "GND_119") (pintype "unspecified"))
      (node (ref "CORE1") (pin "125") (pinfunction "GND_125") (pintype "unspecified"))
      (node (ref "CORE1") (pin "19") (pinfunction "GND_19") (pintype "unspecified"))
      (node (ref "CORE1") (pin "24") (pinfunction "GND_24") (pintype "unspecified"))
      (node (ref "CORE1") (pin "27") (pinfunction "GND_27") (pintype "unspecified"))
      (node (ref "CORE1") (pin "44") (pinfunction "GND_44") (pintype "unspecified"))
      (node (ref "CORE1") (pin "5") (pinfunction "GND_5") (pintype "unspecified"))
      (node (ref "CORE1") (pin "53") (pinfunction "GND_53") (pintype "unspecified"))
      (node (ref "CORE1") (pin "6") (pinfunction "GND_6") (pintype "unspecified"))
      (node (ref "CORE1") (pin "62") (pinfunction "GND_62") (pintype "unspecified"))
      (node (ref "CORE1") (pin "7") (pinfunction "GND_7") (pintype "unspecified"))
      (node (ref "CORE1") (pin "8") (pinfunction "GND_8") (pintype "unspecified"))
      (node (ref "CORE1") (pin "92") (pinfunction "GND_92") (pintype "unspecified"))
      (node (ref "D10") (pin "2") (pinfunction "A_2") (pintype "unspecified"))
      (node (ref "D3") (pin "2") (pinfunction "A_2") (pintype "unspecified"))
      (node (ref "D4") (pin "2") (pinfunction "A_2") (pintype "unspecified"))
      (node (ref "D6") (pin "2") (pinfunction "A_2") (pintype "unspecified"))
      (node (ref "D7") (pin "2") (pinfunction "A_2") (pintype "unspecified"))
      (node (ref "D9") (pin "2") (pinfunction "2_2") (pintype "unspecified"))
      (node (ref "DC1") (pin "2") (pinfunction "2_2") (pintype "input"))
      (node (ref "DC1") (pin "3") (pinfunction "3_3") (pintype "input"))
      (node (ref "DC1") (pin "4") (pinfunction "4_4") (pintype "input"))
      (node (ref "DC1") (pin "5") (pinfunction "5_5") (pintype "input"))
      (node (ref "GE_LAN1") (pin "P10") (pinfunction "P10_P10") (pintype "unspecified"))
      (node (ref "GE_LAN1") (pin "SHIELD0") (pinfunction "SHIELD0_SHIELD0") (pintype "unspecified"))
      (node (ref "GE_LAN1") (pin "SHIELD1") (pinfunction "SHIELD1_SHIELD1") (pintype "unspecified"))
      (node (ref "GE_LAN2") (pin "P10") (pinfunction "P10_P10") (pintype "unspecified"))
      (node (ref "GE_LAN2") (pin "SHIELD0") (pinfunction "SHIELD0_SHIELD0") (pintype "unspecified"))
      (node (ref "GE_LAN2") (pin "SHIELD1") (pinfunction "SHIELD1_SHIELD1") (pintype "unspecified"))
      (node (ref "GE_WAN") (pin "P10") (pinfunction "P10_P10") (pintype "unspecified"))
      (node (ref "GE_WAN") (pin "SHIELD0") (pinfunction "SHIELD0_SHIELD0") (pintype "unspecified"))
      (node (ref "GE_WAN") (pin "SHIELD1") (pinfunction "SHIELD1_SHIELD1") (pintype "unspecified"))
      (node (ref "I2C_1") (pin "2") (pinfunction "2_2") (pintype "unspecified"))
      (node (ref "LED_12V") (pin "1") (pinfunction "K_1") (pintype "input"))
      (node (ref "PCIE1") (pin "15") (pinfunction "GND_15") (pintype "input"))
      (node (ref "PCIE1") (pin "21") (pinfunction "GND_21") (pintype "input"))
      (node (ref "PCIE1") (pin "26") (pinfunction "GND_26") (pintype "input"))
      (node (ref "PCIE1") (pin "27") (pinfunction "GND_27") (pintype "input"))
      (node (ref "PCIE1") (pin "29") (pinfunction "GND_29") (pintype "input"))
      (node (ref "PCIE1") (pin "34") (pinfunction "GND_34") (pintype "input"))
      (node (ref "PCIE1") (pin "35") (pinfunction "GND_35") (pintype "input"))
      (node (ref "PCIE1") (pin "37") (pinfunction "GND_37") (pintype "input"))
      (node (ref "PCIE1") (pin "4") (pinfunction "GND_4") (pintype "input"))
      (node (ref "PCIE1") (pin "40") (pinfunction "GND_40") (pintype "input"))
      (node (ref "PCIE1") (pin "43") (pinfunction "GND_43") (pintype "input"))
      (node (ref "PCIE1") (pin "50") (pinfunction "GND_50") (pintype "input"))
      (node (ref "PCIE1") (pin "9") (pinfunction "GND_9") (pintype "input"))
      (node (ref "PCIE1") (pin "S") (pinfunction "S_S") (pintype "input"))
      (node (ref "PCIE2") (pin "15") (pinfunction "GND_15") (pintype "input"))
      (node (ref "PCIE2") (pin "21") (pinfunction "GND_21") (pintype "input"))
      (node (ref "PCIE2") (pin "26") (pinfunction "GND_26") (pintype "input"))
      (node (ref "PCIE2") (pin "27") (pinfunction "GND_27") (pintype "input"))
      (node (ref "PCIE2") (pin "29") (pinfunction "GND_29") (pintype "input"))
      (node (ref "PCIE2") (pin "34") (pinfunction "GND_34") (pintype "input"))
      (node (ref "PCIE2") (pin "35") (pinfunction "GND_35") (pintype "input"))
      (node (ref "PCIE2") (pin "37") (pinfunction "GND_37") (pintype "input"))
      (node (ref "PCIE2") (pin "4") (pinfunction "GND_4") (pintype "input"))
      (node (ref "PCIE2") (pin "40") (pinfunction "GND_40") (pintype "input"))
      (node (ref "PCIE2") (pin "43") (pinfunction "GND_43") (pintype "input"))
      (node (ref "PCIE2") (pin "50") (pinfunction "GND_50") (pintype "input"))
      (node (ref "PCIE2") (pin "9") (pinfunction "GND_9") (pintype "input"))
      (node (ref "PCIE2") (pin "S") (pinfunction "S_S") (pintype "input"))
      (node (ref "Q1") (pin "2") (pinfunction "E_2") (pintype "input"))
      (node (ref "Q2") (pin "2") (pinfunction "E_2") (pintype "input"))
      (node (ref "Q4") (pin "2") (pinfunction "E_2") (pintype "input"))
      (node (ref "R13") (pin "2") (pinfunction "2_2") (pintype "input"))
      (node (ref "R15") (pin "1") (pinfunction "1_1") (pintype "input"))
      (node (ref "R16") (pin "1") (pinfunction "1_1") (pintype "input"))
      (node (ref "R18") (pin "1") (pinfunction "1_1") (pintype "input"))
      (node (ref "R3") (pin "1") (pinfunction "1_1") (pintype "input"))
      (node (ref "R38") (pin "2") (pinfunction "2_2") (pintype "input"))
      (node (ref "R5") (pin "3") (pinfunction "3_3") (pintype "unspecified"))
      (node (ref "SIM1") (pin "10") (pinfunction "10_10") (pintype "input"))
      (node (ref "SIM1") (pin "11") (pinfunction "11_11") (pintype "input"))
      (node (ref "SIM1") (pin "8") (pinfunction "8_8") (pintype "input"))
      (node (ref "SIM1") (pin "9") (pinfunction "9_9") (pintype "input"))
      (node (ref "SIM1") (pin "C5") (pinfunction "GND_C5") (pintype "input"))
      (node (ref "TP1") (pin "1") (pinfunction "1_1") (pintype "input"))
      (node (ref "TTL1") (pin "2") (pinfunction "2_2") (pintype "unspecified"))
      (node (ref "TTL2") (pin "2") (pinfunction "2_2") (pintype "unspecified"))
      (node (ref "U1") (pin "4") (pinfunction "V-_4") (pintype "unspecified"))
      (node (ref "U2") (pin "1") (pinfunction "AGND_1") (pintype "unspecified"))
      (node (ref "U2") (pin "4") (pinfunction "GND_4") (pintype "unspecified"))
      (node (ref "U3") (pin "1") (pinfunction "GND_1") (pintype "input"))
      (node (ref "U4") (pin "1") (pinfunction "A1_1") (pintype "unspecified"))
      (node (ref "U4") (pin "2") (pinfunction "A0_2") (pintype "unspecified"))
      (node (ref "U4") (pin "7") (pinfunction "GND_7") (pintype "unspecified"))
      (node (ref "U5") (pin "5") (pinfunction "GND_5") (pintype "unspecified"))
      (node (ref "U6") (pin "2") (pinfunction "2_2") (pintype "input"))
      (node (ref "U7") (pin "2") (pinfunction "2_2") (pintype "input"))
      (node (ref "USB1") (pin "4") (pinfunction "4_4") (pintype "unspecified"))
      (node (ref "WWAN1") (pin "11") (pinfunction "GND_11") (pintype "input"))
      (node (ref "WWAN1") (pin "27") (pinfunction "GND_27") (pintype "input"))
      (node (ref "WWAN1") (pin "3") (pinfunction "GND_3") (pintype "input"))
      (node (ref "WWAN1") (pin "33") (pinfunction "GND_33") (pintype "input"))
      (node (ref "WWAN1") (pin "39") (pinfunction "GND_39") (pintype "input"))
      (node (ref "WWAN1") (pin "45") (pinfunction "GND_45") (pintype "input"))
      (node (ref "WWAN1") (pin "5") (pinfunction "GND_5") (pintype "input"))
      (node (ref "WWAN1") (pin "51") (pinfunction "GND_51") (pintype "input"))
      (node (ref "WWAN1") (pin "57") (pinfunction "GND_57") (pintype "input"))
      (node (ref "WWAN1") (pin "71") (pinfunction "GND_71") (pintype "input"))
      (node (ref "WWAN1") (pin "73") (pinfunction "GND_73") (pintype "input"))
      (node (ref "WWAN1") (pin "S") (pinfunction "S_S") (pintype "input"))
    )
    (net (code "48") (name "GPIO13") (class "Default")
      (node (ref "CORE1") (pin "121") (pinfunction "JTDO_121") (pintype "unspecified"))
      (node (ref "R39") (pin "2") (pinfunction "2_2") (pintype "input"))
    )
    (net (code "49") (name "GPIO14") (class "Default")
      (node (ref "CORE1") (pin "122") (pinfunction "JTDI_122") (pintype "unspecified"))
      (node (ref "R41") (pin "2") (pinfunction "2_2") (pintype "input"))
    )
    (net (code "50") (name "GPIO15") (class "Default")
      (node (ref "CORE1") (pin "120") (pinfunction "JTMS_120") (pintype "unspecified"))
      (node (ref "R43") (pin "1") (pinfunction "1_1") (pintype "input"))
    )
    (net (code "51") (name "GPIO16") (class "Default")
      (node (ref "CORE1") (pin "124") (pinfunction "JTCLK_124") (pintype "unspecified"))
      (node (ref "Q4") (pin "3") (pinfunction "C_3") (pintype "input"))
      (node (ref "R27") (pin "1") (pinfunction "1_1") (pintype "input"))
    )
    (net (code "52") (name "GPIO17") (class "Default")
      (node (ref "CORE1") (pin "123") (pinfunction "JTRST_N_123") (pintype "unspecified"))
      (node (ref "R28") (pin "1") (pinfunction "1_1") (pintype "input"))
    )
    (net (code "53") (name "I2C_SCL") (class "Default")
      (node (ref "CORE1") (pin "96") (pinfunction "I2C_SCLK_96") (pintype "unspecified"))
      (node (ref "I2C_1") (pin "4") (pinfunction "4_4") (pintype "unspecified"))
      (node (ref "R25") (pin "1") (pinfunction "1_1") (pintype "input"))
      (node (ref "U4") (pin "5") (pinfunction "SCL_5") (pintype "unspecified"))
      (node (ref "U5") (pin "3") (pinfunction "SCL_3") (pintype "unspecified"))
    )
    (net (code "54") (name "I2C_SDA") (class "Default")
      (node (ref "CORE1") (pin "97") (pinfunction "I2C_SD_97") (pintype "unspecified"))
      (node (ref "I2C_1") (pin "3") (pinfunction "3_3") (pintype "unspecified"))
      (node (ref "R24") (pin "1") (pinfunction "1_1") (pintype "input"))
      (node (ref "U4") (pin "4") (pinfunction "SDA_4") (pintype "unspecified"))
      (node (ref "U5") (pin "4") (pinfunction "SDA_4") (pintype "unspecified"))
    )
    (net (code "55") (name "LED_P0") (class "Default")
      (node (ref "CORE1") (pin "75") (pinfunction "ESW_P0_LED_0_75") (pintype "unspecified"))
    )
    (net (code "56") (name "LED_P1") (class "Default")
      (node (ref "CORE1") (pin "74") (pinfunction "ESW_P1_LED_0_74") (pintype "unspecified"))
      (node (ref "R40") (pin "2") (pinfunction "2_2") (pintype "input"))
    )
    (net (code "57") (name "LED_P2") (class "Default")
      (node (ref "CORE1") (pin "73") (pinfunction "ESW_P2_LED_0_73") (pintype "unspecified"))
      (node (ref "R42") (pin "2") (pinfunction "2_2") (pintype "input"))
    )
    (net (code "58") (name "LED_P3") (class "Default")
      (node (ref "CORE1") (pin "72") (pinfunction "ESW_P3_LED_0_72") (pintype "unspecified"))
    )
    (net (code "59") (name "LED_P4") (class "Default")
      (node (ref "CORE1") (pin "71") (pinfunction "ESW_P4_LED_0_71") (pintype "unspecified"))
      (node (ref "R44") (pin "2") (pinfunction "2_2") (pintype "input"))
    )
    (net (code "60") (name "LED_WLAN1") (class "Default")
      (node (ref "PCIE1") (pin "44") (pinfunction "~LED_WLAN_44") (pintype "bidirectional"))
    )
    (net (code "61") (name "LED_WLAN2") (class "Default")
      (node (ref "PCIE2") (pin "44") (pinfunction "~LED_WLAN_44") (pintype "bidirectional"))
    )
    (net (code "62") (name "LED_WWAN") (class "Default")
      (node (ref "WWAN1") (pin "10") (pinfunction "GPIO_9/DAS/DSS_10") (pintype "input"))
    )
    (net (code "63") (name "Net-(12VOUT1-Pad1)") (class "Default")
      (node (ref "12VOUT1") (pin "1") (pinfunction "1_1") (pintype "unspecified"))
      (node (ref "FH1") (pin "1") (pinfunction "1_1") (pintype "input"))
    )
    (net (code "64") (name "Net-(C5-Pad2)") (class "Default")
      (node (ref "C5") (pin "2") (pinfunction "2_2") (pintype "input"))
      (node (ref "R5") (pin "2") (pinfunction "2_2") (pintype "unspecified"))
      (node (ref "R6") (pin "1") (pinfunction "1_1") (pintype "input"))
      (node (ref "U1") (pin "3") (pinfunction "+IN_3") (pintype "unspecified"))
    )
    (net (code "65") (name "Net-(C15-Pad2)") (class "Default")
      (node (ref "C15") (pin "2") (pinfunction "2_2") (pintype "input"))
      (node (ref "R21") (pin "1") (pinfunction "1_1") (pintype "input"))
    )
    (net (code "66") (name "Net-(C29-Pad1)") (class "Default")
      (node (ref "C29") (pin "1") (pinfunction "1_1") (pintype "input"))
      (node (ref "GE_LAN1") (pin "P1") (pinfunction "P1_P1") (pintype "unspecified"))
    )
    (net (code "67") (name "Net-(C30-Pad1)") (class "Default")
      (node (ref "C30") (pin "1") (pinfunction "1_1") (pintype "input"))
      (node (ref "GE_LAN2") (pin "P1") (pinfunction "P1_P1") (pintype "unspecified"))
    )
    (net (code "68") (name "Net-(C31-Pad1)") (class "Default")
      (node (ref "C31") (pin "1") (pinfunction "1_1") (pintype "input"))
      (node (ref "GE_WAN") (pin "P1") (pinfunction "P1_P1") (pintype "unspecified"))
    )
    (net (code "69") (name "Net-(D5-A)") (class "Default")
      (node (ref "CAR_IN") (pin "2") (pinfunction "2_2") (pintype "unspecified"))
      (node (ref "D5") (pin "2") (pinfunction "A_2") (pintype "unspecified"))
    )
    (net (code "70") (name "Net-(D7-K)") (class "Default")
      (node (ref "D7") (pin "1") (pinfunction "K_1") (pintype "unspecified"))
      (node (ref "R4") (pin "2") (pinfunction "2_2") (pintype "input"))
      (node (ref "U1") (pin "2") (pinfunction "-IN_2") (pintype "unspecified"))
    )
    (net (code "71") (name "Net-(D8-K)") (class "Default")
      (node (ref "D8") (pin "1") (pinfunction "K_1") (pintype "unspecified"))
      (node (ref "R6") (pin "2") (pinfunction "2_2") (pintype "input"))
    )
    (net (code "72") (name "Net-(F1-Pad2)") (class "Default")
      (node (ref "F1") (pin "2") (pinfunction "2_2") (pintype "unspecified"))
      (node (ref "I2C_1") (pin "1") (pinfunction "1_1") (pintype "unspecified"))
    )
    (net (code "73") (name "Net-(F2-Pad2)") (class "Default")
      (node (ref "F2") (pin "2") (pinfunction "2_2") (pintype "unspecified"))
      (node (ref "TTL2") (pin "1") (pinfunction "1_1") (pintype "unspecified"))
    )
    (net (code "74") (name "Net-(F3-Pad2)") (class "Default")
      (node (ref "F3") (pin "2") (pinfunction "2_2") (pintype "unspecified"))
      (node (ref "USB1") (pin "1") (pinfunction "1_1") (pintype "unspecified"))
    )
    (net (code "75") (name "Net-(GE_LAN1-Pad12)") (class "Default")
      (node (ref "GE_LAN1") (pin "12") (pinfunction "12_12") (pintype "unspecified"))
      (node (ref "R40") (pin "1") (pinfunction "1_1") (pintype "input"))
    )
    (net (code "76") (name "Net-(GE_LAN1-Pad13)") (class "Default")
      (node (ref "GE_LAN1") (pin "13") (pinfunction "13_13") (pintype "unspecified"))
      (node (ref "R39") (pin "1") (pinfunction "1_1") (pintype "input"))
    )
    (net (code "77") (name "Net-(GE_LAN2-Pad12)") (class "Default")
      (node (ref "GE_LAN2") (pin "12") (pinfunction "12_12") (pintype "unspecified"))
      (node (ref "R42") (pin "1") (pinfunction "1_1") (pintype "input"))
    )
    (net (code "78") (name "Net-(GE_LAN2-Pad13)") (class "Default")
      (node (ref "GE_LAN2") (pin "13") (pinfunction "13_13") (pintype "unspecified"))
      (node (ref "R41") (pin "1") (pinfunction "1_1") (pintype "input"))
    )
    (net (code "79") (name "Net-(GE_WAN-Pad12)") (class "Default")
      (node (ref "GE_WAN") (pin "12") (pinfunction "12_12") (pintype "unspecified"))
      (node (ref "R44") (pin "1") (pinfunction "1_1") (pintype "input"))
    )
    (net (code "80") (name "Net-(GE_WAN-Pad13)") (class "Default")
      (node (ref "GE_WAN") (pin "13") (pinfunction "13_13") (pintype "unspecified"))
      (node (ref "R43") (pin "2") (pinfunction "2_2") (pintype "input"))
    )
    (net (code "81") (name "Net-(LED_12V-A)") (class "Default")
      (node (ref "LED_12V") (pin "2") (pinfunction "A_2") (pintype "input"))
      (node (ref "R2") (pin "2") (pinfunction "2_2") (pintype "input"))
    )
    (net (code "82") (name "Net-(PCIE1-+5V-Pad45)") (class "Default")
      (node (ref "PCIE1") (pin "45") (pinfunction "+5V_45") (pintype "input"))
      (node (ref "PCIE1") (pin "47") (pinfunction "+5V_47") (pintype "input"))
      (node (ref "R30") (pin "2") (pinfunction "2_2") (pintype "input"))
    )
    (net (code "83") (name "Net-(PCIE1-+5V-Pad49)") (class "Default")
      (node (ref "PCIE1") (pin "49") (pinfunction "+5V_49") (pintype "input"))
      (node (ref "PCIE1") (pin "51") (pinfunction "+5V_51") (pintype "input"))
      (node (ref "R29") (pin "2") (pinfunction "2_2") (pintype "input"))
    )
    (net (code "84") (name "Net-(PCIE1-~PERST)") (class "Default")
      (node (ref "PCIE1") (pin "22") (pinfunction "~PERST_22") (pintype "bidirectional"))
      (node (ref "R31") (pin "1") (pinfunction "1_1") (pintype "input"))
    )
    (net (code "85") (name "Net-(PCIE2-+5V-Pad45)") (class "Default")
      (node (ref "PCIE2") (pin "45") (pinfunction "+5V_45") (pintype "input"))
      (node (ref "PCIE2") (pin "47") (pinfunction "+5V_47") (pintype "input"))
      (node (ref "R33") (pin "2") (pinfunction "2_2") (pintype "input"))
    )
    (net (code "86") (name "Net-(PCIE2-+5V-Pad49)") (class "Default")
      (node (ref "PCIE2") (pin "49") (pinfunction "+5V_49") (pintype "input"))
      (node (ref "PCIE2") (pin "51") (pinfunction "+5V_51") (pintype "input"))
      (node (ref "R32") (pin "2") (pinfunction "2_2") (pintype "input"))
    )
    (net (code "87") (name "Net-(PCIE2-~PERST)") (class "Default")
      (node (ref "PCIE2") (pin "22") (pinfunction "~PERST_22") (pintype "bidirectional"))
      (node (ref "R34") (pin "1") (pinfunction "1_1") (pintype "input"))
    )
    (net (code "88") (name "Net-(Q1-B)") (class "Default")
      (node (ref "Q1") (pin "1") (pinfunction "B_1") (pintype "input"))
      (node (ref "R7") (pin "2") (pinfunction "2_2") (pintype "input"))
    )
    (net (code "89") (name "Net-(Q1-C)") (class "Default")
      (node (ref "Q1") (pin "3") (pinfunction "C_3") (pintype "input"))
      (node (ref "R9") (pin "2") (pinfunction "2_2") (pintype "input"))
    )
    (net (code "90") (name "Net-(Q2-B)") (class "Default")
      (node (ref "Q2") (pin "1") (pinfunction "B_1") (pintype "input"))
      (node (ref "R8") (pin "2") (pinfunction "2_2") (pintype "input"))
    )
    (net (code "91") (name "Net-(Q2-C)") (class "Default")
      (node (ref "Q2") (pin "3") (pinfunction "C_3") (pintype "input"))
      (node (ref "R10") (pin "1") (pinfunction "1_1") (pintype "input"))
    )
    (net (code "92") (name "Net-(Q3-G)") (class "Default")
      (node (ref "C6") (pin "2") (pinfunction "2_2") (pintype "input"))
      (node (ref "Q3") (pin "1") (pinfunction "G_1") (pintype "unspecified"))
      (node (ref "R10") (pin "2") (pinfunction "2_2") (pintype "input"))
      (node (ref "R11") (pin "2") (pinfunction "2_2") (pintype "input"))
      (node (ref "R9") (pin "1") (pinfunction "1_1") (pintype "input"))
    )
    (net (code "93") (name "Net-(Q4-B)") (class "Default")
      (node (ref "Q4") (pin "1") (pinfunction "B_1") (pintype "input"))
      (node (ref "R26") (pin "2") (pinfunction "2_2") (pintype "input"))
    )
    (net (code "94") (name "Net-(R7-Pad1)") (class "Default")
      (node (ref "R7") (pin "1") (pinfunction "1_1") (pintype "input"))
      (node (ref "U1") (pin "1") (pinfunction "OUT_1") (pintype "unspecified"))
    )
    (net (code "95") (name "Net-(R16-Pad2)") (class "Default")
      (node (ref "R16") (pin "2") (pinfunction "2_2") (pintype "input"))
      (node (ref "R19") (pin "1") (pinfunction "1_1") (pintype "input"))
      (node (ref "R20") (pin "1") (pinfunction "1_1") (pintype "input"))
    )
    (net (code "96") (name "Net-(R23-Pad2)") (class "Default")
      (node (ref "R23") (pin "2") (pinfunction "2_2") (pintype "input"))
      (node (ref "TTL1") (pin "3") (pinfunction "3_3") (pintype "unspecified"))
    )
    (net (code "97") (name "Net-(U2-BST)") (class "Default")
      (node (ref "C9") (pin "1") (pinfunction "1_1") (pintype "input"))
      (node (ref "U2") (pin "5") (pinfunction "BST_5") (pintype "unspecified"))
    )
    (net (code "98") (name "Net-(U2-EN{slash}SYNC)") (class "Default")
      (node (ref "R12") (pin "1") (pinfunction "1_1") (pintype "input"))
      (node (ref "R13") (pin "1") (pinfunction "1_1") (pintype "input"))
      (node (ref "U2") (pin "6") (pinfunction "EN/SYNC_6") (pintype "unspecified"))
    )
    (net (code "99") (name "Net-(U2-FB)") (class "Default")
      (node (ref "C13") (pin "2") (pinfunction "2_2") (pintype "input"))
      (node (ref "R14") (pin "2") (pinfunction "2_2") (pintype "input"))
      (node (ref "R15") (pin "2") (pinfunction "2_2") (pintype "input"))
      (node (ref "U2") (pin "8") (pinfunction "FB_8") (pintype "unspecified"))
    )
    (net (code "100") (name "Net-(U2-SW)") (class "Default")
      (node (ref "C9") (pin "2") (pinfunction "2_2") (pintype "input"))
      (node (ref "L1") (pin "1") (pinfunction "1_1") (pintype "unspecified"))
      (node (ref "U2") (pin "3") (pinfunction "SW_3") (pintype "unspecified"))
    )
    (net (code "101") (name "Net-(U2-VCC)") (class "Default")
      (node (ref "C14") (pin "2") (pinfunction "2_2") (pintype "unspecified"))
      (node (ref "U2") (pin "7") (pinfunction "VCC_7") (pintype "unspecified"))
    )
    (net (code "102") (name "Net-(U3-BS)") (class "Default")
      (node (ref "R21") (pin "2") (pinfunction "2_2") (pintype "input"))
      (node (ref "U3") (pin "6") (pinfunction "BS_6") (pintype "input"))
    )
    (net (code "103") (name "Net-(U3-EN)") (class "Default")
      (node (ref "R17") (pin "2") (pinfunction "2_2") (pintype "input"))
      (node (ref "R18") (pin "2") (pinfunction "2_2") (pintype "input"))
      (node (ref "U3") (pin "5") (pinfunction "EN_5") (pintype "input"))
    )
    (net (code "104") (name "Net-(U3-FB)") (class "Default")
      (node (ref "R19") (pin "2") (pinfunction "2_2") (pintype "input"))
      (node (ref "U3") (pin "4") (pinfunction "FB_4") (pintype "input"))
    )
    (net (code "105") (name "Net-(U3-SW)") (class "Default")
      (node (ref "C15") (pin "1") (pinfunction "1_1") (pintype "input"))
      (node (ref "L2") (pin "1") (pinfunction "1_1") (pintype "unspecified"))
      (node (ref "U3") (pin "2") (pinfunction "SW_2") (pintype "input"))
    )
    (net (code "106") (name "Net-(U4-VS+)") (class "Default")
      (node (ref "C21") (pin "1") (pinfunction "1_1") (pintype "input"))
      (node (ref "R22") (pin "1") (pinfunction "1_1") (pintype "input"))
      (node (ref "U4") (pin "6") (pinfunction "VS+_6") (pintype "unspecified"))
      (node (ref "U5") (pin "2") (pinfunction "VDD_2") (pintype "unspecified"))
    )
    (net (code "107") (name "Net-(WWAN1-FULL_CARD_POWER_OFF#)") (class "Default")
      (node (ref "R35") (pin "2") (pinfunction "2_2") (pintype "input"))
      (node (ref "WWAN1") (pin "6") (pinfunction "FULL_CARD_POWER_OFF#_6") (pintype "input"))
    )
    (net (code "108") (name "Net-(WWAN1-PERST#)") (class "Default")
      (node (ref "R36") (pin "1") (pinfunction "1_1") (pintype "input"))
      (node (ref "WWAN1") (pin "50") (pinfunction "PERST#_50") (pintype "input"))
    )
    (net (code "109") (name "PCIE0_REFCLK+") (class "Default")
      (node (ref "CORE1") (pin "117") (pinfunction "PCIE_CKP0_117") (pintype "unspecified"))
      (node (ref "PCIE1") (pin "13") (pinfunction "RefClk+_13") (pintype "input"))
    )
    (net (code "110") (name "PCIE0_REFCLK-") (class "Default")
      (node (ref "CORE1") (pin "118") (pinfunction "PCIE_CKN0_118") (pintype "unspecified"))
      (node (ref "PCIE1") (pin "11") (pinfunction "RefClk-_11") (pintype "input"))
    )
    (net (code "111") (name "PCIE0_RX+") (class "Default")
      (node (ref "CORE1") (pin "114") (pinfunction "PCIE_RXN0_114") (pintype "unspecified"))
      (node (ref "PCIE1") (pin "25") (pinfunction "PERp0_25") (pintype "input"))
    )
    (net (code "112") (name "PCIE0_RX-") (class "Default")
      (node (ref "CORE1") (pin "113") (pinfunction "PCIE_RXP0_113") (pintype "unspecified"))
      (node (ref "PCIE1") (pin "23") (pinfunction "PERn0_23") (pintype "input"))
    )
    (net (code "113") (name "PCIE0_TX+") (class "Default")
      (node (ref "CORE1") (pin "116") (pinfunction "PCIE_TXP0_116") (pintype "unspecified"))
      (node (ref "PCIE1") (pin "33") (pinfunction "PETp0_33") (pintype "input"))
    )
    (net (code "114") (name "PCIE0_TX-") (class "Default")
      (node (ref "CORE1") (pin "115") (pinfunction "PCIE_TXN0_115") (pintype "unspecified"))
      (node (ref "PCIE1") (pin "31") (pinfunction "PETn0_31") (pintype "input"))
    )
    (net (code "115") (name "PCIE1_REFCLK+") (class "Default")
      (node (ref "CORE1") (pin "111") (pinfunction "PCIE_CKP1_111") (pintype "unspecified"))
      (node (ref "PCIE2") (pin "13") (pinfunction "RefClk+_13") (pintype "input"))
    )
    (net (code "116") (name "PCIE1_REFCLK-") (class "Default")
      (node (ref "CORE1") (pin "110") (pinfunction "PCIE_CKN1_110") (pintype "unspecified"))
      (node (ref "PCIE2") (pin "11") (pinfunction "RefClk-_11") (pintype "input"))
    )
    (net (code "117") (name "PCIE1_RX+") (class "Default")
      (node (ref "CORE1") (pin "108") (pinfunction "PCIE_RXP1_108") (pintype "unspecified"))
      (node (ref "PCIE2") (pin "25") (pinfunction "PERp0_25") (pintype "input"))
    )
    (net (code "118") (name "PCIE1_RX-") (class "Default")
      (node (ref "CORE1") (pin "109") (pinfunction "PCIE_RXN1_109") (pintype "unspecified"))
      (node (ref "PCIE2") (pin "23") (pinfunction "PERn0_23") (pintype "input"))
    )
    (net (code "119") (name "PCIE1_TX+") (class "Default")
      (node (ref "CORE1") (pin "106") (pinfunction "PCIE_TXP1_106") (pintype "unspecified"))
      (node (ref "PCIE2") (pin "33") (pinfunction "PETp0_33") (pintype "input"))
    )
    (net (code "120") (name "PCIE1_TX-") (class "Default")
      (node (ref "CORE1") (pin "107") (pinfunction "PCIE_TXN1_107") (pintype "unspecified"))
      (node (ref "PCIE2") (pin "31") (pinfunction "PETn0_31") (pintype "input"))
    )
    (net (code "121") (name "PCIE2_REFCLK+") (class "Default")
      (node (ref "CORE1") (pin "103") (pinfunction "PCIE_CKP2_103") (pintype "unspecified"))
      (node (ref "WWAN1") (pin "55") (pinfunction "REFCLK+_55") (pintype "input"))
    )
    (net (code "122") (name "PCIE2_REFCLK-") (class "Default")
      (node (ref "CORE1") (pin "102") (pinfunction "PCIE_CKN2_102") (pintype "unspecified"))
      (node (ref "WWAN1") (pin "53") (pinfunction "REFCLK-_53") (pintype "input"))
    )
    (net (code "123") (name "PCIE2_RX+") (class "Default")
      (node (ref "CORE1") (pin "100") (pinfunction "PCIE_RXN2_100") (pintype "unspecified"))
      (node (ref "WWAN1") (pin "43") (pinfunction "RX0p/SATA_B-_43") (pintype "input"))
    )
    (net (code "124") (name "PCIE2_RX-") (class "Default")
      (node (ref "CORE1") (pin "101") (pinfunction "PCIE_RXP2_101") (pintype "unspecified"))
      (node (ref "WWAN1") (pin "41") (pinfunction "RX0n/SATA_B+_41") (pintype "input"))
    )
    (net (code "125") (name "PCIE2_TX+") (class "Default")
      (node (ref "CORE1") (pin "98") (pinfunction "PCIE_TXN2_98") (pintype "unspecified"))
      (node (ref "WWAN1") (pin "49") (pinfunction "TX0p/SATA_A+_49") (pintype "input"))
    )
    (net (code "126") (name "PCIE2_TX-") (class "Default")
      (node (ref "CORE1") (pin "99") (pinfunction "PCIE_TXP2_99") (pintype "unspecified"))
      (node (ref "WWAN1") (pin "47") (pinfunction "TX0n/SATA_A-_47") (pintype "input"))
    )
    (net (code "127") (name "PERST") (class "Default")
      (node (ref "CORE1") (pin "105") (pinfunction "PERST_N_105") (pintype "unspecified"))
      (node (ref "R31") (pin "2") (pinfunction "2_2") (pintype "input"))
      (node (ref "R34") (pin "2") (pinfunction "2_2") (pintype "input"))
      (node (ref "R36") (pin "2") (pinfunction "2_2") (pintype "input"))
    )
    (net (code "128") (name "RST_BTN") (class "Default")
      (node (ref "CORE1") (pin "112") (pinfunction "WDT_RST_N_112") (pintype "unspecified"))
      (node (ref "TP2") (pin "1") (pinfunction "1_1") (pintype "input"))
    )
    (net (code "129") (name "SENSE_V+") (class "Default")
      (node (ref "CAR_IN") (pin "1") (pinfunction "1_1") (pintype "unspecified"))
      (node (ref "DC1") (pin "1") (pinfunction "1_1") (pintype "input"))
      (node (ref "R1") (pin "2") (pinfunction "2_2") (pintype "unspecified"))
      (node (ref "U4") (pin "10") (pinfunction "VIN+_10") (pintype "unspecified"))
    )
    (net (code "130") (name "SENSE_V-") (class "Default")
      (node (ref "D1") (pin "2") (pinfunction "A_2") (pintype "unspecified"))
      (node (ref "D2") (pin "1") (pinfunction "A_1") (pintype "unspecified"))
      (node (ref "D2") (pin "3") (pinfunction "A_3") (pintype "unspecified"))
      (node (ref "R1") (pin "1") (pinfunction "1_1") (pintype "unspecified"))
      (node (ref "U4") (pin "8") (pinfunction "VBUS_8") (pintype "unspecified"))
      (node (ref "U4") (pin "9") (pinfunction "VIN-_9") (pintype "unspecified"))
    )
    (net (code "131") (name "SERIAL_RXD1") (class "Default")
      (node (ref "CORE1") (pin "93") (pinfunction "RXD1_93") (pintype "unspecified"))
      (node (ref "R23") (pin "1") (pinfunction "1_1") (pintype "input"))
    )
    (net (code "132") (name "SERIAL_RXD2") (class "Default")
      (node (ref "CORE1") (pin "11") (pinfunction "RXD2_11") (pintype "unspecified"))
      (node (ref "TTL2") (pin "3") (pinfunction "3_3") (pintype "unspecified"))
    )
    (net (code "133") (name "SERIAL_RXD3") (class "Default")
      (node (ref "CORE1") (pin "13") (pinfunction "RXD3_13") (pintype "unspecified"))
    )
    (net (code "134") (name "SERIAL_TXD1") (class "Default")
      (node (ref "CORE1") (pin "94") (pinfunction "TXD1_94") (pintype "unspecified"))
      (node (ref "TTL1") (pin "4") (pinfunction "4_4") (pintype "unspecified"))
    )
    (net (code "135") (name "SERIAL_TXD2") (class "Default")
      (node (ref "CORE1") (pin "10") (pinfunction "TXD2_10") (pintype "unspecified"))
      (node (ref "TTL2") (pin "4") (pinfunction "4_4") (pintype "unspecified"))
    )
    (net (code "136") (name "SERIAL_TXD3") (class "Default")
      (node (ref "CORE1") (pin "12") (pinfunction "TXD3_12") (pintype "unspecified"))
    )
    (net (code "137") (name "UIM_CLK") (class "Default")
      (node (ref "C28") (pin "1") (pinfunction "1_1") (pintype "input"))
      (node (ref "SIM1") (pin "C3") (pinfunction "CLK_C3") (pintype "input"))
      (node (ref "U6") (pin "4") (pinfunction "4_4") (pintype "input"))
      (node (ref "WWAN1") (pin "32") (pinfunction "UIM_CLK_32") (pintype "input"))
    )
    (net (code "138") (name "UIM_DAT") (class "Default")
      (node (ref "C27") (pin "1") (pinfunction "1_1") (pintype "input"))
      (node (ref "R37") (pin "1") (pinfunction "1_1") (pintype "input"))
      (node (ref "SIM1") (pin "C7") (pinfunction "I/O_C7") (pintype "input"))
      (node (ref "U6") (pin "6") (pinfunction "6_6") (pintype "input"))
      (node (ref "WWAN1") (pin "34") (pinfunction "UIM_DATA_34") (pintype "input"))
    )
    (net (code "139") (name "UIM_DET") (class "Default")
      (node (ref "R38") (pin "1") (pinfunction "1_1") (pintype "input"))
      (node (ref "SIM1") (pin "CD") (pinfunction "CD_CD") (pintype "input"))
      (node (ref "U6") (pin "3") (pinfunction "3_3") (pintype "input"))
      (node (ref "WWAN1") (pin "66") (pinfunction "SIM_DETCET_66") (pintype "input"))
    )
    (net (code "140") (name "UIM_PWR") (class "Default")
      (node (ref "C25") (pin "1") (pinfunction "1_1") (pintype "input"))
      (node (ref "R37") (pin "2") (pinfunction "2_2") (pintype "input"))
      (node (ref "SIM1") (pin "C1") (pinfunction "VCC_C1") (pintype "input"))
      (node (ref "WWAN1") (pin "36") (pinfunction "UIM_PWR_36") (pintype "input"))
    )
    (net (code "141") (name "UIM_RST") (class "Default")
      (node (ref "C26") (pin "2") (pinfunction "2_2") (pintype "input"))
      (node (ref "SIM1") (pin "C2") (pinfunction "RST_C2") (pintype "input"))
      (node (ref "U6") (pin "1") (pinfunction "1_1") (pintype "input"))
      (node (ref "WWAN1") (pin "30") (pinfunction "UIM_RESET_30") (pintype "input"))
    )
    (net (code "142") (name "USB3_DM") (class "Default")
      (node (ref "CORE1") (pin "26") (pinfunction "USB_DM_P0_26") (pintype "unspecified"))
      (node (ref "L3") (pin "3") (pinfunction "3_3") (pintype "unspecified"))
    )
    (net (code "143") (name "USB3_DP") (class "Default")
      (node (ref "CORE1") (pin "25") (pinfunction "USB_DP_P0_25") (pintype "unspecified"))
      (node (ref "L3") (pin "4") (pinfunction "4_4") (pintype "unspecified"))
    )
    (net (code "144") (name "USB3_RX+") (class "Default")
      (node (ref "CORE1") (pin "22") (pinfunction "SSUSB_RXP_22") (pintype "unspecified"))
    )
    (net (code "145") (name "USB3_RX-") (class "Default")
      (node (ref "CORE1") (pin "23") (pinfunction "SSUSB_RXN_23") (pintype "unspecified"))
    )
    (net (code "146") (name "USB3_TX+") (class "Default")
      (node (ref "CORE1") (pin "20") (pinfunction "SSUSB_TXP_20") (pintype "unspecified"))
    )
    (net (code "147") (name "USB3_TX-") (class "Default")
      (node (ref "CORE1") (pin "21") (pinfunction "SSUSB_TXN_21") (pintype "unspecified"))
    )
    (net (code "148") (name "USBPORT_DM") (class "Default")
      (node (ref "L3") (pin "2") (pinfunction "2_2") (pintype "unspecified"))
      (node (ref "U7") (pin "3") (pinfunction "3_3") (pintype "input"))
      (node (ref "USB1") (pin "2") (pinfunction "2_2") (pintype "unspecified"))
    )
    (net (code "149") (name "USBPORT_DP") (class "Default")
      (node (ref "L3") (pin "1") (pinfunction "1_1") (pintype "unspecified"))
      (node (ref "U7") (pin "4") (pinfunction "4_4") (pintype "input"))
      (node (ref "USB1") (pin "3") (pinfunction "3_3") (pintype "unspecified"))
    )
    (net (code "150") (name "USB_LTE_DM") (class "Default")
      (node (ref "CORE1") (pin "18") (pinfunction "USB_DM_1P_18") (pintype "unspecified"))
      (node (ref "WWAN1") (pin "9") (pinfunction "USB_D-_9") (pintype "input"))
    )
    (net (code "151") (name "USB_LTE_DP") (class "Default")
      (node (ref "CORE1") (pin "17") (pinfunction "USB_DP_1P_17") (pintype "unspecified"))
      (node (ref "WWAN1") (pin "7") (pinfunction "USB_D+_7") (pintype "input"))
    )
    (net (code "152") (name "unconnected-(CORE1-CTS2_N-Pad15)") (class "Default")
      (node (ref "CORE1") (pin "15") (pinfunction "CTS2_N_15") (pintype "unspecified"))
    )
    (net (code "153") (name "unconnected-(CORE1-CTS3_N-Pad9)") (class "Default")
      (node (ref "CORE1") (pin "9") (pinfunction "CTS3_N_9") (pintype "unspecified"))
    )
    (net (code "154") (name "unconnected-(CORE1-ESW_DBG_B-Pad81)") (class "Default")
      (node (ref "CORE1") (pin "81") (pinfunction "ESW_DBG_B_81") (pintype "unspecified"))
    )
    (net (code "155") (name "unconnected-(CORE1-ESW_DTEST-Pad76)") (class "Default")
      (node (ref "CORE1") (pin "76") (pinfunction "ESW_DTEST_76") (pintype "unspecified"))
    )
    (net (code "156") (name "unconnected-(CORE1-GE2_RXCLK-Pad91)") (class "Default")
      (node (ref "CORE1") (pin "91") (pinfunction "GE2_RXCLK_91") (pintype "unspecified"))
    )
    (net (code "157") (name "unconnected-(CORE1-GE2_RXD0-Pad89)") (class "Default")
      (node (ref "CORE1") (pin "89") (pinfunction "GE2_RXD0_89") (pintype "unspecified"))
    )
    (net (code "158") (name "unconnected-(CORE1-GE2_RXD1-Pad88)") (class "Default")
      (node (ref "CORE1") (pin "88") (pinfunction "GE2_RXD1_88") (pintype "unspecified"))
    )
    (net (code "159") (name "unconnected-(CORE1-GE2_RXD2-Pad87)") (class "Default")
      (node (ref "CORE1") (pin "87") (pinfunction "GE2_RXD2_87") (pintype "unspecified"))
    )
    (net (code "160") (name "unconnected-(CORE1-GE2_RXD3-Pad86)") (class "Default")
      (node (ref "CORE1") (pin "86") (pinfunction "GE2_RXD3_86") (pintype "unspecified"))
    )
    (net (code "161") (name "unconnected-(CORE1-GE2_RXDV-Pad90)") (class "Default")
      (node (ref "CORE1") (pin "90") (pinfunction "GE2_RXDV_90") (pintype "unspecified"))
    )
    (net (code "162") (name "unconnected-(CORE1-GE2_TXCLK-Pad85)") (class "Default")
      (node (ref "CORE1") (pin "85") (pinfunction "GE2_TXCLK_85") (pintype "unspecified"))
    )
    (net (code "163") (name "unconnected-(CORE1-GE2_TXD0-Pad80)") (class "Default")
      (node (ref "CORE1") (pin "80") (pinfunction "GE2_TXD0_80") (pintype "unspecified"))
    )
    (net (code "164") (name "unconnected-(CORE1-GE2_TXD1-Pad79)") (class "Default")
      (node (ref "CORE1") (pin "79") (pinfunction "GE2_TXD1_79") (pintype "unspecified"))
    )
    (net (code "165") (name "unconnected-(CORE1-GE2_TXD2-Pad78)") (class "Default")
      (node (ref "CORE1") (pin "78") (pinfunction "GE2_TXD2_78") (pintype "unspecified"))
    )
    (net (code "166") (name "unconnected-(CORE1-GE2_TXD3-Pad77)") (class "Default")
      (node (ref "CORE1") (pin "77") (pinfunction "GE2_TXD3_77") (pintype "unspecified"))
    )
    (net (code "167") (name "unconnected-(CORE1-GE2_TXEN-Pad84)") (class "Default")
      (node (ref "CORE1") (pin "84") (pinfunction "GE2_TXEN_84") (pintype "unspecified"))
    )
    (net (code "168") (name "unconnected-(CORE1-GPIO0-Pad104)") (class "Default")
      (node (ref "CORE1") (pin "104") (pinfunction "GPIO0_104") (pintype "unspecified"))
    )
    (net (code "169") (name "unconnected-(CORE1-MDC-Pad83)") (class "Default")
      (node (ref "CORE1") (pin "83") (pinfunction "MDC_83") (pintype "unspecified"))
    )
    (net (code "170") (name "unconnected-(CORE1-MDIO-Pad82)") (class "Default")
      (node (ref "CORE1") (pin "82") (pinfunction "MDIO_82") (pintype "unspecified"))
    )
    (net (code "171") (name "unconnected-(CORE1-ND_ALE-Pad138)") (class "Default")
      (node (ref "CORE1") (pin "138") (pinfunction "ND_ALE_138") (pintype "unspecified"))
    )
    (net (code "172") (name "unconnected-(CORE1-ND_CLE-Pad137)") (class "Default")
      (node (ref "CORE1") (pin "137") (pinfunction "ND_CLE_137") (pintype "unspecified"))
    )
    (net (code "173") (name "unconnected-(CORE1-ND_CS_N-Pad136)") (class "Default")
      (node (ref "CORE1") (pin "136") (pinfunction "ND_CS_N_136") (pintype "unspecified"))
    )
    (net (code "174") (name "unconnected-(CORE1-ND_D0-Pad133)") (class "Default")
      (node (ref "CORE1") (pin "133") (pinfunction "ND_D0_133") (pintype "unspecified"))
    )
    (net (code "175") (name "unconnected-(CORE1-ND_D1-Pad132)") (class "Default")
      (node (ref "CORE1") (pin "132") (pinfunction "ND_D1_132") (pintype "unspecified"))
    )
    (net (code "176") (name "unconnected-(CORE1-ND_D2-Pad131)") (class "Default")
      (node (ref "CORE1") (pin "131") (pinfunction "ND_D2_131") (pintype "unspecified"))
    )
    (net (code "177") (name "unconnected-(CORE1-ND_D3-Pad130)") (class "Default")
      (node (ref "CORE1") (pin "130") (pinfunction "ND_D3_130") (pintype "unspecified"))
    )
    (net (code "178") (name "unconnected-(CORE1-ND_D4-Pad129)") (class "Default")
      (node (ref "CORE1") (pin "129") (pinfunction "ND_D4_129") (pintype "unspecified"))
    )
    (net (code "179") (name "unconnected-(CORE1-ND_D5-Pad128)") (class "Default")
      (node (ref "CORE1") (pin "128") (pinfunction "ND_D5_128") (pintype "unspecified"))
    )
    (net (code "180") (name "unconnected-(CORE1-ND_D6-Pad127)") (class "Default")
      (node (ref "CORE1") (pin "127") (pinfunction "ND_D6_127") (pintype "unspecified"))
    )
    (net (code "181") (name "unconnected-(CORE1-ND_D7-Pad126)") (class "Default")
      (node (ref "CORE1") (pin "126") (pinfunction "ND_D7_126") (pintype "unspecified"))
    )
    (net (code "182") (name "unconnected-(CORE1-ND_RB_N-Pad134)") (class "Default")
      (node (ref "CORE1") (pin "134") (pinfunction "ND_RB_N_134") (pintype "unspecified"))
    )
    (net (code "183") (name "unconnected-(CORE1-ND_RE_N-Pad135)") (class "Default")
      (node (ref "CORE1") (pin "135") (pinfunction "ND_RE_N_135") (pintype "unspecified"))
    )
    (net (code "184") (name "unconnected-(CORE1-ND_WE_N-Pad139)") (class "Default")
      (node (ref "CORE1") (pin "139") (pinfunction "ND_WE_N_139") (pintype "unspecified"))
    )
    (net (code "185") (name "unconnected-(CORE1-ND_WP-Pad140)") (class "Default")
      (node (ref "CORE1") (pin "140") (pinfunction "ND_WP_140") (pintype "unspecified"))
    )
    (net (code "186") (name "unconnected-(CORE1-PORST_N-Pad95)") (class "Default")
      (node (ref "CORE1") (pin "95") (pinfunction "PORST_N_95") (pintype "unspecified"))
    )
    (net (code "187") (name "unconnected-(CORE1-RTS2_N-Pad14)") (class "Default")
      (node (ref "CORE1") (pin "14") (pinfunction "RTS2_N_14") (pintype "unspecified"))
    )
    (net (code "188") (name "unconnected-(CORE1-RTS3_N-Pad16)") (class "Default")
      (node (ref "CORE1") (pin "16") (pinfunction "RTS3_N_16") (pintype "unspecified"))
    )
    (net (code "189") (name "unconnected-(PCIE1-+1.5V-Pad6)") (class "Default")
      (node (ref "PCIE1") (pin "6") (pinfunction "+1.5V_6") (pintype "input"))
    )
    (net (code "190") (name "unconnected-(PCIE1-+1.5V-Pad28)") (class "Default")
      (node (ref "PCIE1") (pin "28") (pinfunction "+1.5V_28") (pintype "input"))
    )
    (net (code "191") (name "unconnected-(PCIE1-+1.5V-Pad48)") (class "Default")
      (node (ref "PCIE1") (pin "48") (pinfunction "+1.5V_48") (pintype "input"))
    )
    (net (code "192") (name "unconnected-(PCIE1-+3.3Aux-Pad39)") (class "Default")
      (node (ref "PCIE1") (pin "39") (pinfunction "+3.3Aux_39") (pintype "input"))
    )
    (net (code "193") (name "unconnected-(PCIE1-+3.3Aux-Pad41)") (class "Default")
      (node (ref "PCIE1") (pin "41") (pinfunction "+3.3Aux_41") (pintype "input"))
    )
    (net (code "194") (name "unconnected-(PCIE1-COEX1-Pad3)") (class "Default")
      (node (ref "PCIE1") (pin "3") (pinfunction "COEX1_3") (pintype "input"))
    )
    (net (code "195") (name "unconnected-(PCIE1-COEX2-Pad5)") (class "Default")
      (node (ref "PCIE1") (pin "5") (pinfunction "COEX2_5") (pintype "input"))
    )
    (net (code "196") (name "unconnected-(PCIE1-GND-Pad18)") (class "Default")
      (node (ref "PCIE1") (pin "18") (pinfunction "GND_18") (pintype "input"))
    )
    (net (code "197") (name "unconnected-(PCIE1-SMB_CLK-Pad30)") (class "Default")
      (node (ref "PCIE1") (pin "30") (pinfunction "SMB_CLK_30") (pintype "bidirectional"))
    )
    (net (code "198") (name "unconnected-(PCIE1-SMB_DATA-Pad32)") (class "Default")
      (node (ref "PCIE1") (pin "32") (pinfunction "SMB_DATA_32") (pintype "input"))
    )
    (net (code "199") (name "unconnected-(PCIE1-UIM_C4-Pad19)") (class "Default")
      (node (ref "PCIE1") (pin "19") (pinfunction "UIM_C4_19") (pintype "input"))
    )
    (net (code "200") (name "unconnected-(PCIE1-UIM_C8-Pad17)") (class "Default")
      (node (ref "PCIE1") (pin "17") (pinfunction "UIM_C8_17") (pintype "input"))
    )
    (net (code "201") (name "unconnected-(PCIE1-UIM_CLK-Pad12)") (class "Default")
      (node (ref "PCIE1") (pin "12") (pinfunction "UIM_CLK_12") (pintype "bidirectional"))
    )
    (net (code "202") (name "unconnected-(PCIE1-UIM_DATA-Pad10)") (class "Default")
      (node (ref "PCIE1") (pin "10") (pinfunction "UIM_DATA_10") (pintype "input"))
    )
    (net (code "203") (name "unconnected-(PCIE1-UIM_PWR-Pad8)") (class "Default")
      (node (ref "PCIE1") (pin "8") (pinfunction "UIM_PWR_8") (pintype "input"))
    )
    (net (code "204") (name "unconnected-(PCIE1-UIM_RESET-Pad14)") (class "Default")
      (node (ref "PCIE1") (pin "14") (pinfunction "UIM_RESET_14") (pintype "input"))
    )
    (net (code "205") (name "unconnected-(PCIE1-UIM_VPP-Pad16)") (class "Default")
      (node (ref "PCIE1") (pin "16") (pinfunction "UIM_VPP_16") (pintype "input"))
    )
    (net (code "206") (name "unconnected-(PCIE1-USB_D+-Pad38)") (class "Default")
      (node (ref "PCIE1") (pin "38") (pinfunction "USB_D+_38") (pintype "input"))
    )
    (net (code "207") (name "unconnected-(PCIE1-USB_D--Pad36)") (class "Default")
      (node (ref "PCIE1") (pin "36") (pinfunction "USB_D-_36") (pintype "input"))
    )
    (net (code "208") (name "unconnected-(PCIE1-~CLKREQ-Pad7)") (class "Default")
      (node (ref "PCIE1") (pin "7") (pinfunction "~CLKREQ_7") (pintype "input"))
    )
    (net (code "209") (name "unconnected-(PCIE1-~LED_WPAN-Pad46)") (class "Default")
      (node (ref "PCIE1") (pin "46") (pinfunction "~LED_WPAN_46") (pintype "bidirectional"))
    )
    (net (code "210") (name "unconnected-(PCIE1-~LED_WWAN-Pad42)") (class "Default")
      (node (ref "PCIE1") (pin "42") (pinfunction "~LED_WWAN_42") (pintype "bidirectional"))
    )
    (net (code "211") (name "unconnected-(PCIE1-~WAKE-Pad1)") (class "Default")
      (node (ref "PCIE1") (pin "1") (pinfunction "~WAKE_1") (pintype "input"))
    )
    (net (code "212") (name "unconnected-(PCIE1-~W_DISABLE-Pad20)") (class "Default")
      (node (ref "PCIE1") (pin "20") (pinfunction "~W_DISABLE_20") (pintype "bidirectional"))
    )
    (net (code "213") (name "unconnected-(PCIE2-+1.5V-Pad6)") (class "Default")
      (node (ref "PCIE2") (pin "6") (pinfunction "+1.5V_6") (pintype "input"))
    )
    (net (code "214") (name "unconnected-(PCIE2-+1.5V-Pad28)") (class "Default")
      (node (ref "PCIE2") (pin "28") (pinfunction "+1.5V_28") (pintype "input"))
    )
    (net (code "215") (name "unconnected-(PCIE2-+1.5V-Pad48)") (class "Default")
      (node (ref "PCIE2") (pin "48") (pinfunction "+1.5V_48") (pintype "input"))
    )
    (net (code "216") (name "unconnected-(PCIE2-+3.3Aux-Pad39)") (class "Default")
      (node (ref "PCIE2") (pin "39") (pinfunction "+3.3Aux_39") (pintype "input"))
    )
    (net (code "217") (name "unconnected-(PCIE2-+3.3Aux-Pad41)") (class "Default")
      (node (ref "PCIE2") (pin "41") (pinfunction "+3.3Aux_41") (pintype "input"))
    )
    (net (code "218") (name "unconnected-(PCIE2-COEX1-Pad3)") (class "Default")
      (node (ref "PCIE2") (pin "3") (pinfunction "COEX1_3") (pintype "input"))
    )
    (net (code "219") (name "unconnected-(PCIE2-COEX2-Pad5)") (class "Default")
      (node (ref "PCIE2") (pin "5") (pinfunction "COEX2_5") (pintype "input"))
    )
    (net (code "220") (name "unconnected-(PCIE2-GND-Pad18)") (class "Default")
      (node (ref "PCIE2") (pin "18") (pinfunction "GND_18") (pintype "input"))
    )
    (net (code "221") (name "unconnected-(PCIE2-SMB_CLK-Pad30)") (class "Default")
      (node (ref "PCIE2") (pin "30") (pinfunction "SMB_CLK_30") (pintype "bidirectional"))
    )
    (net (code "222") (name "unconnected-(PCIE2-SMB_DATA-Pad32)") (class "Default")
      (node (ref "PCIE2") (pin "32") (pinfunction "SMB_DATA_32") (pintype "input"))
    )
    (net (code "223") (name "unconnected-(PCIE2-UIM_C4-Pad19)") (class "Default")
      (node (ref "PCIE2") (pin "19") (pinfunction "UIM_C4_19") (pintype "input"))
    )
    (net (code "224") (name "unconnected-(PCIE2-UIM_C8-Pad17)") (class "Default")
      (node (ref "PCIE2") (pin "17") (pinfunction "UIM_C8_17") (pintype "input"))
    )
    (net (code "225") (name "unconnected-(PCIE2-UIM_CLK-Pad12)") (class "Default")
      (node (ref "PCIE2") (pin "12") (pinfunction "UIM_CLK_12") (pintype "bidirectional"))
    )
    (net (code "226") (name "unconnected-(PCIE2-UIM_DATA-Pad10)") (class "Default")
      (node (ref "PCIE2") (pin "10") (pinfunction "UIM_DATA_10") (pintype "input"))
    )
    (net (code "227") (name "unconnected-(PCIE2-UIM_PWR-Pad8)") (class "Default")
      (node (ref "PCIE2") (pin "8") (pinfunction "UIM_PWR_8") (pintype "input"))
    )
    (net (code "228") (name "unconnected-(PCIE2-UIM_RESET-Pad14)") (class "Default")
      (node (ref "PCIE2") (pin "14") (pinfunction "UIM_RESET_14") (pintype "input"))
    )
    (net (code "229") (name "unconnected-(PCIE2-UIM_VPP-Pad16)") (class "Default")
      (node (ref "PCIE2") (pin "16") (pinfunction "UIM_VPP_16") (pintype "input"))
    )
    (net (code "230") (name "unconnected-(PCIE2-USB_D+-Pad38)") (class "Default")
      (node (ref "PCIE2") (pin "38") (pinfunction "USB_D+_38") (pintype "input"))
    )
    (net (code "231") (name "unconnected-(PCIE2-USB_D--Pad36)") (class "Default")
      (node (ref "PCIE2") (pin "36") (pinfunction "USB_D-_36") (pintype "input"))
    )
    (net (code "232") (name "unconnected-(PCIE2-~CLKREQ-Pad7)") (class "Default")
      (node (ref "PCIE2") (pin "7") (pinfunction "~CLKREQ_7") (pintype "input"))
    )
    (net (code "233") (name "unconnected-(PCIE2-~LED_WPAN-Pad46)") (class "Default")
      (node (ref "PCIE2") (pin "46") (pinfunction "~LED_WPAN_46") (pintype "bidirectional"))
    )
    (net (code "234") (name "unconnected-(PCIE2-~LED_WWAN-Pad42)") (class "Default")
      (node (ref "PCIE2") (pin "42") (pinfunction "~LED_WWAN_42") (pintype "bidirectional"))
    )
    (net (code "235") (name "unconnected-(PCIE2-~WAKE-Pad1)") (class "Default")
      (node (ref "PCIE2") (pin "1") (pinfunction "~WAKE_1") (pintype "input"))
    )
    (net (code "236") (name "unconnected-(PCIE2-~W_DISABLE-Pad20)") (class "Default")
      (node (ref "PCIE2") (pin "20") (pinfunction "~W_DISABLE_20") (pintype "bidirectional"))
    )
    (net (code "237") (name "unconnected-(SIM1-VPP-PadC6)") (class "Default")
      (node (ref "SIM1") (pin "C6") (pinfunction "VPP_C6") (pintype "input"))
    )
    (net (code "238") (name "unconnected-(U1-+IN-Pad5)") (class "Default")
      (node (ref "U1") (pin "5") (pinfunction "+IN_5") (pintype "unspecified"))
    )
    (net (code "239") (name "unconnected-(U1--IN-Pad6)") (class "Default")
      (node (ref "U1") (pin "6") (pinfunction "-IN_6") (pintype "unspecified"))
    )
    (net (code "240") (name "unconnected-(U1-OUT-Pad7)") (class "Default")
      (node (ref "U1") (pin "7") (pinfunction "OUT_7") (pintype "unspecified"))
    )
    (net (code "241") (name "unconnected-(U4-Alert-Pad3)") (class "Default")
      (node (ref "U4") (pin "3") (pinfunction "Alert_3") (pintype "unspecified"))
    )
    (net (code "242") (name "unconnected-(U5-NC-Pad1)") (class "Default")
      (node (ref "U5") (pin "1") (pinfunction "NC_1") (pintype "unspecified"))
    )
    (net (code "243") (name "unconnected-(U5-NC-Pad6)") (class "Default")
      (node (ref "U5") (pin "6") (pinfunction "NC_6") (pintype "unspecified"))
    )
    (net (code "244") (name "unconnected-(U6-Pad5)") (class "Default")
      (node (ref "U6") (pin "5") (pinfunction "5_5") (pintype "input"))
    )
    (net (code "245") (name "unconnected-(U7-Pad1)") (class "Default")
      (node (ref "U7") (pin "1") (pinfunction "1_1") (pintype "input"))
    )
    (net (code "246") (name "unconnected-(U7-Pad5)") (class "Default")
      (node (ref "U7") (pin "5") (pinfunction "5_5") (pintype "input"))
    )
    (net (code "247") (name "unconnected-(U7-Pad6)") (class "Default")
      (node (ref "U7") (pin "6") (pinfunction "6_6") (pintype "input"))
    )
    (net (code "248") (name "unconnected-(WWAN1-ALERT#{slash}GPIO_2-Pad44)") (class "Default")
      (node (ref "WWAN1") (pin "44") (pinfunction "ALERT#/GPIO_2_44") (pintype "input"))
    )
    (net (code "249") (name "unconnected-(WWAN1-ANTCTL0-Pad59)") (class "Default")
      (node (ref "WWAN1") (pin "59") (pinfunction "ANTCTL0_59") (pintype "input"))
    )
    (net (code "250") (name "unconnected-(WWAN1-ANTCTL1-Pad61)") (class "Default")
      (node (ref "WWAN1") (pin "61") (pinfunction "ANTCTL1_61") (pintype "input"))
    )
    (net (code "251") (name "unconnected-(WWAN1-ANTCTL2-Pad63)") (class "Default")
      (node (ref "WWAN1") (pin "63") (pinfunction "ANTCTL2_63") (pintype "input"))
    )
    (net (code "252") (name "unconnected-(WWAN1-ANTCTL3-Pad65)") (class "Default")
      (node (ref "WWAN1") (pin "65") (pinfunction "ANTCTL3_65") (pintype "input"))
    )
    (net (code "253") (name "unconnected-(WWAN1-CLKREQ#-Pad52)") (class "Default")
      (node (ref "WWAN1") (pin "52") (pinfunction "CLKREQ#_52") (pintype "input"))
    )
    (net (code "254") (name "unconnected-(WWAN1-COEX3-Pad60)") (class "Default")
      (node (ref "WWAN1") (pin "60") (pinfunction "COEX3_60") (pintype "input"))
    )
    (net (code "255") (name "unconnected-(WWAN1-COEX_RXD{slash}COEX1-Pad64)") (class "Default")
      (node (ref "WWAN1") (pin "64") (pinfunction "COEX_RXD/COEX1_64") (pintype "input"))
    )
    (net (code "256") (name "unconnected-(WWAN1-COEX_TXD{slash}COEX2-Pad62)") (class "Default")
      (node (ref "WWAN1") (pin "62") (pinfunction "COEX_TXD/COEX2_62") (pintype "input"))
    )
    (net (code "257") (name "unconnected-(WWAN1-CONFIG_0-Pad21)") (class "Default")
      (node (ref "WWAN1") (pin "21") (pinfunction "CONFIG_0_21") (pintype "input"))
    )
    (net (code "258") (name "unconnected-(WWAN1-CONFIG_1-Pad69)") (class "Default")
      (node (ref "WWAN1") (pin "69") (pinfunction "CONFIG_1_69") (pintype "input"))
    )
    (net (code "259") (name "unconnected-(WWAN1-CONFIG_2-Pad75)") (class "Default")
      (node (ref "WWAN1") (pin "75") (pinfunction "CONFIG_2_75") (pintype "input"))
    )
    (net (code "260") (name "unconnected-(WWAN1-CONFIG_3-Pad1)") (class "Default")
      (node (ref "WWAN1") (pin "1") (pinfunction "CONFIG_3_1") (pintype "input"))
    )
    (net (code "261") (name "unconnected-(WWAN1-DEVSLP-Pad38)") (class "Default")
      (node (ref "WWAN1") (pin "38") (pinfunction "DEVSLP_38") (pintype "input"))
    )
    (net (code "262") (name "unconnected-(WWAN1-DPR-Pad25)") (class "Default")
      (node (ref "WWAN1") (pin "25") (pinfunction "DPR_25") (pintype "input"))
    )
    (net (code "263") (name "unconnected-(WWAN1-GPIO_3-Pad46)") (class "Default")
      (node (ref "WWAN1") (pin "46") (pinfunction "GPIO_3_46") (pintype "input"))
    )
    (net (code "264") (name "unconnected-(WWAN1-GPIO_4-Pad48)") (class "Default")
      (node (ref "WWAN1") (pin "48") (pinfunction "GPIO_4_48") (pintype "input"))
    )
    (net (code "265") (name "unconnected-(WWAN1-GPIO_5-Pad20)") (class "Default")
      (node (ref "WWAN1") (pin "20") (pinfunction "GPIO_5_20") (pintype "input"))
    )
    (net (code "266") (name "unconnected-(WWAN1-GPIO_6-Pad22)") (class "Default")
      (node (ref "WWAN1") (pin "22") (pinfunction "GPIO_6_22") (pintype "input"))
    )
    (net (code "267") (name "unconnected-(WWAN1-GPIO_7-Pad24)") (class "Default")
      (node (ref "WWAN1") (pin "24") (pinfunction "GPIO_7_24") (pintype "input"))
    )
    (net (code "268") (name "unconnected-(WWAN1-GPIO_8-Pad28)") (class "Default")
      (node (ref "WWAN1") (pin "28") (pinfunction "GPIO_8_28") (pintype "input"))
    )
    (net (code "269") (name "unconnected-(WWAN1-GPIO_10-Pad26)") (class "Default")
      (node (ref "WWAN1") (pin "26") (pinfunction "GPIO_10_26") (pintype "input"))
    )
    (net (code "270") (name "unconnected-(WWAN1-GPIO_11-Pad23)") (class "Default")
      (node (ref "WWAN1") (pin "23") (pinfunction "GPIO_11_23") (pintype "input"))
    )
    (net (code "271") (name "unconnected-(WWAN1-MFG2{slash}NC-Pad58)") (class "Default")
      (node (ref "WWAN1") (pin "58") (pinfunction "MFG2/NC_58") (pintype "input"))
    )
    (net (code "272") (name "unconnected-(WWAN1-MGF1{slash}NC-Pad56)") (class "Default")
      (node (ref "WWAN1") (pin "56") (pinfunction "MGF1/NC_56") (pintype "input"))
    )
    (net (code "273") (name "unconnected-(WWAN1-PEWAKE#-Pad54)") (class "Default")
      (node (ref "WWAN1") (pin "54") (pinfunction "PEWAKE#_54") (pintype "input"))
    )
    (net (code "274") (name "unconnected-(WWAN1-RESET#-Pad67)") (class "Default")
      (node (ref "WWAN1") (pin "67") (pinfunction "RESET#_67") (pintype "input"))
    )
    (net (code "275") (name "unconnected-(WWAN1-RX1P{slash}USB3_RXp-Pad31)") (class "Default")
      (node (ref "WWAN1") (pin "31") (pinfunction "RX1P/USB3_RXp_31") (pintype "input"))
    )
    (net (code "276") (name "unconnected-(WWAN1-RX1n{slash}USB3_RXn-Pad29)") (class "Default")
      (node (ref "WWAN1") (pin "29") (pinfunction "RX1n/USB3_RXn_29") (pintype "input"))
    )
    (net (code "277") (name "unconnected-(WWAN1-SCL{slash}GPIO_0-Pad40)") (class "Default")
      (node (ref "WWAN1") (pin "40") (pinfunction "SCL/GPIO_0_40") (pintype "input"))
    )
    (net (code "278") (name "unconnected-(WWAN1-SDA{slash}GPIO_1-Pad42)") (class "Default")
      (node (ref "WWAN1") (pin "42") (pinfunction "SDA/GPIO_1_42") (pintype "input"))
    )
    (net (code "279") (name "unconnected-(WWAN1-SUSCLK-Pad68)") (class "Default")
      (node (ref "WWAN1") (pin "68") (pinfunction "SUSCLK_68") (pintype "input"))
    )
    (net (code "280") (name "unconnected-(WWAN1-TX1n{slash}USB3_TXn-Pad35)") (class "Default")
      (node (ref "WWAN1") (pin "35") (pinfunction "TX1n/USB3_TXn_35") (pintype "input"))
    )
    (net (code "281") (name "unconnected-(WWAN1-TX1p{slash}USB3_TXp-Pad37)") (class "Default")
      (node (ref "WWAN1") (pin "37") (pinfunction "TX1p/USB3_TXp_37") (pintype "input"))
    )
    (net (code "282") (name "unconnected-(WWAN1-W_DISABLE#-Pad8)") (class "Default")
      (node (ref "WWAN1") (pin "8") (pinfunction "W_DISABLE#_8") (pintype "input"))
    )
  )
)
